# 8MIC_ximpedance_J007901D.net
KiCad netlist of a schematic drawn in EAGLE
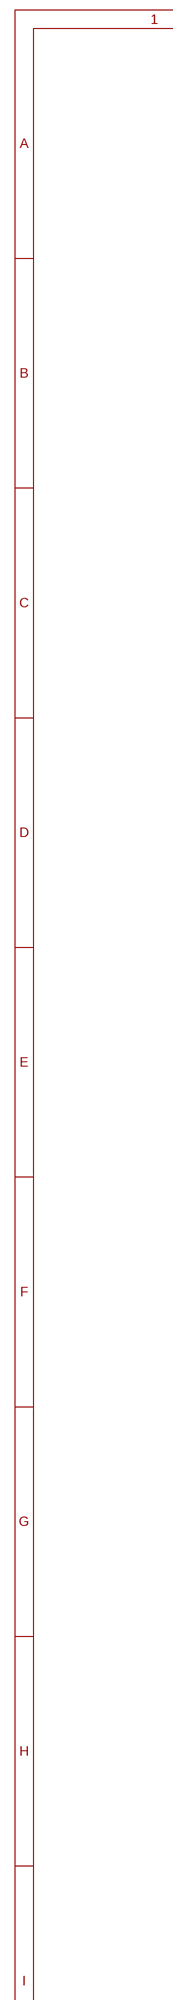
[diagram p0: schematic, sheet 1, part 1 of 2]
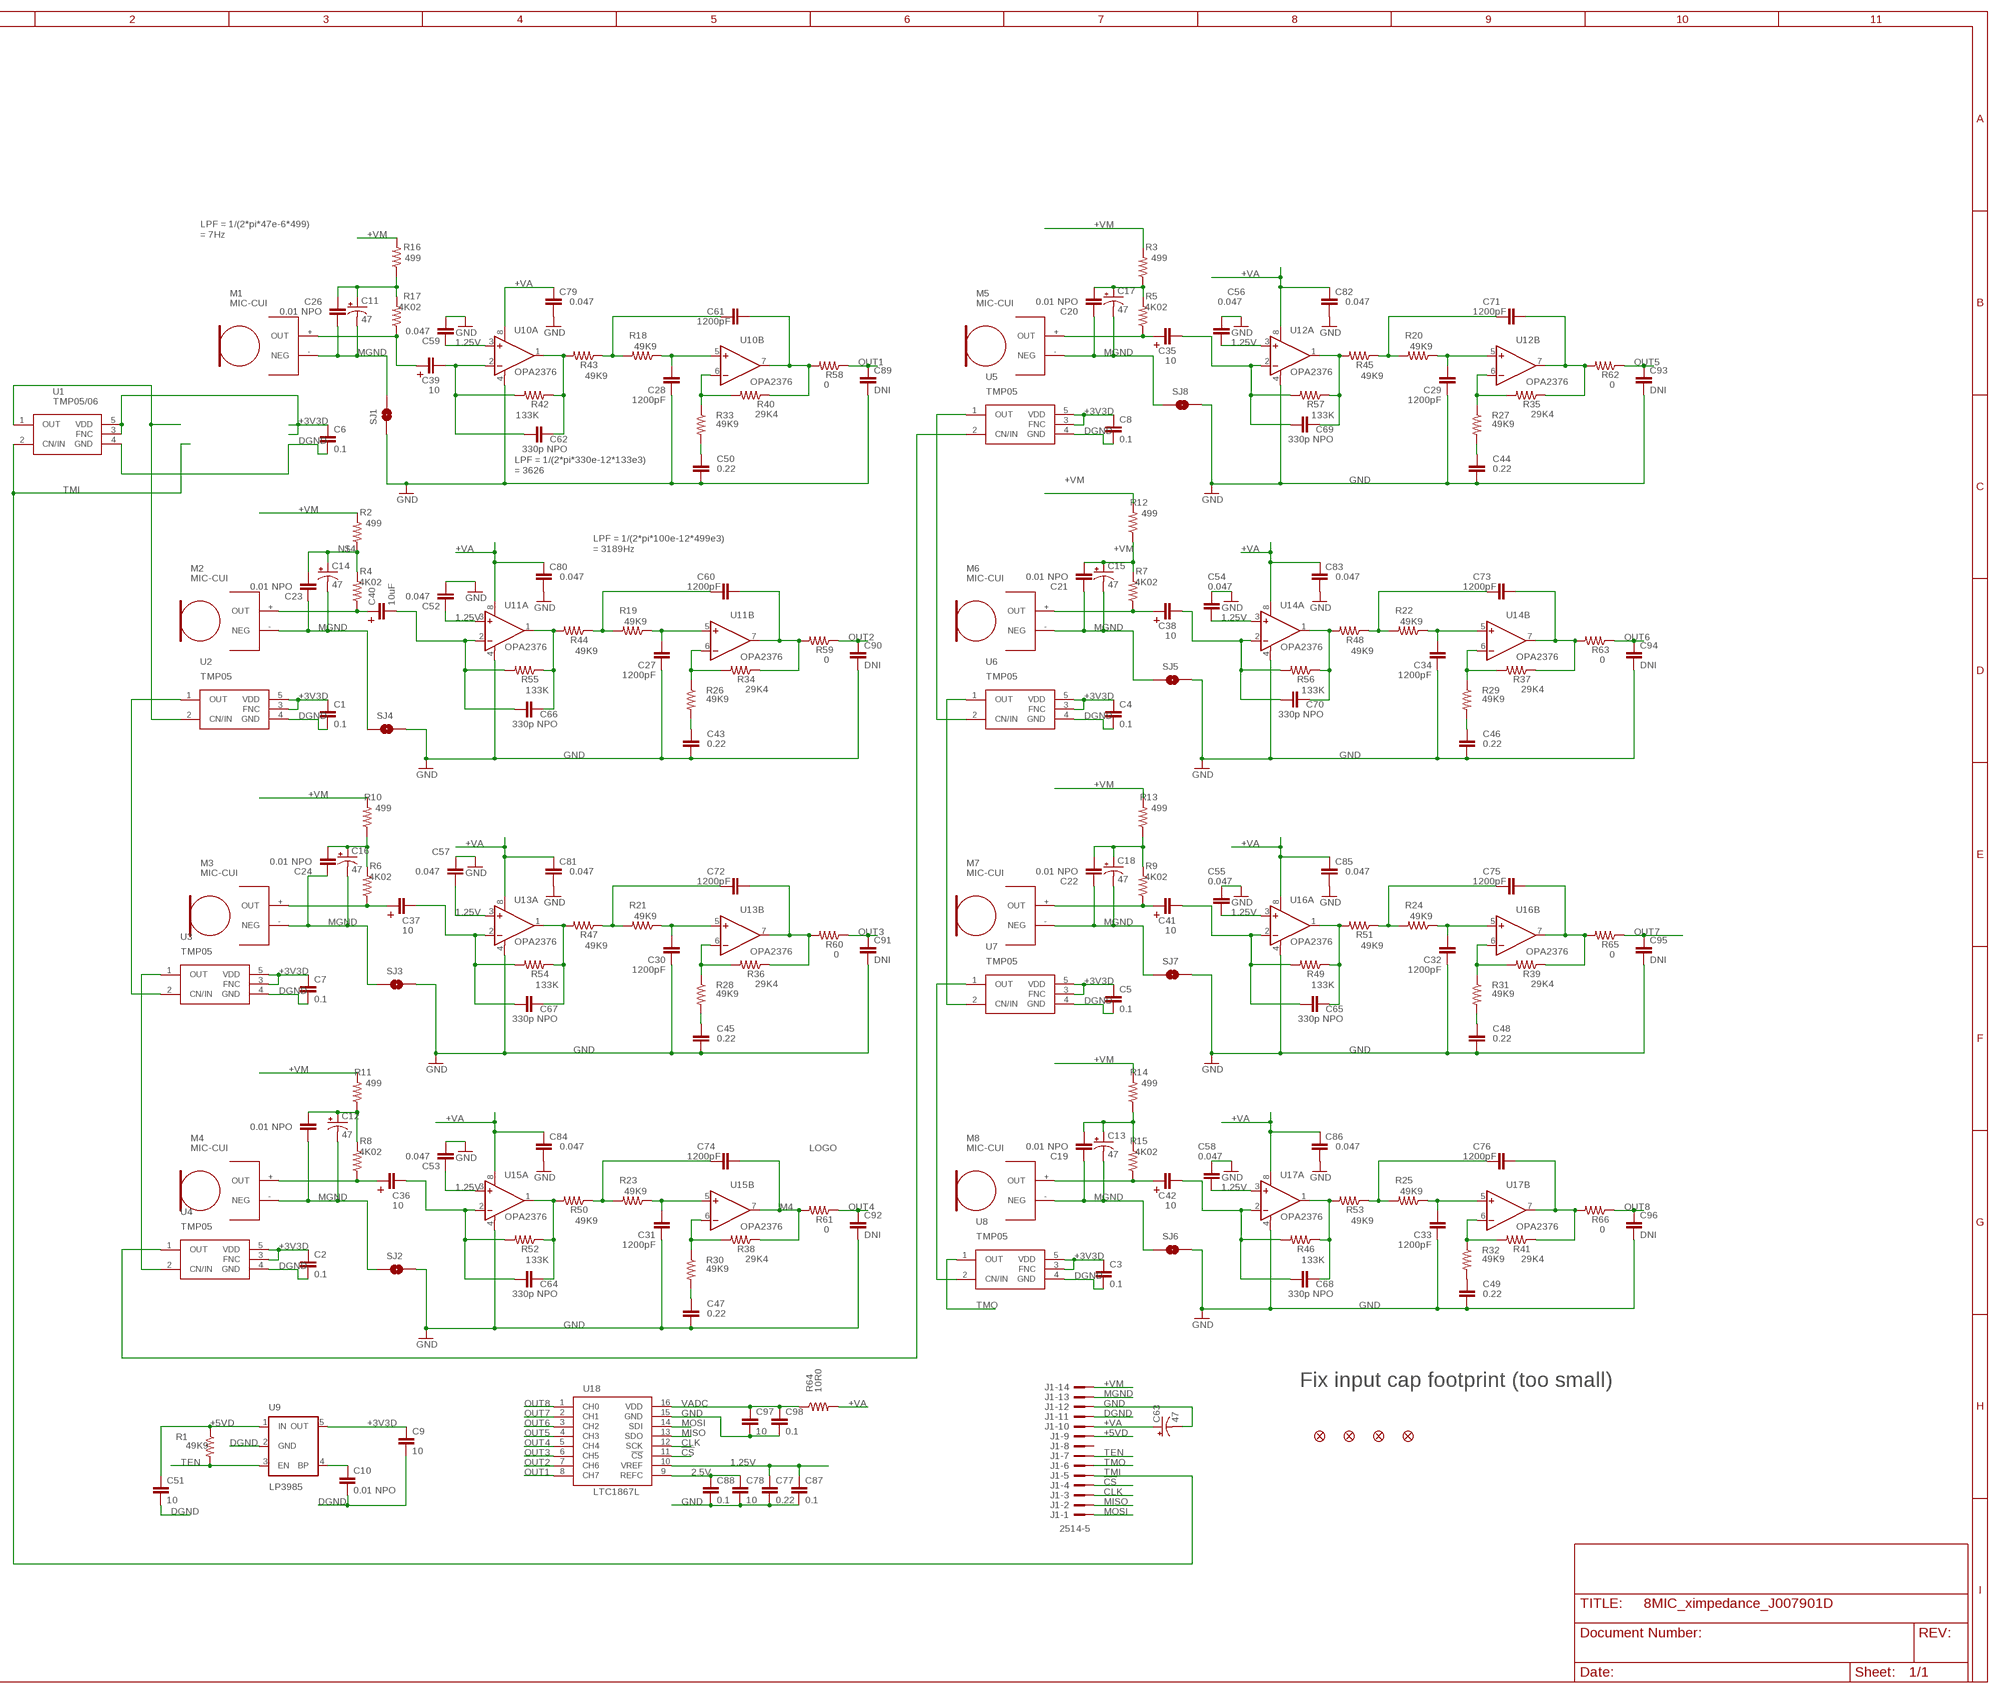
[diagram p1: schematic, sheet 1, part 2 of 2]

(export (version "E")
  (design (tool "Eeschema 10.0.6"))
  (components
    (comp (ref "C1")
      (value "0.1")
      (footprint "eagle-import:0805S")
      (libsource (lib "eagle-import") (part "CAPS0805S"))
    )
    (comp (ref "C2")
      (value "0.1")
      (footprint "eagle-import:0805S")
      (libsource (lib "eagle-import") (part "CAPS0805S"))
    )
    (comp (ref "C3")
      (value "0.1")
      (footprint "eagle-import:0805S")
      (libsource (lib "eagle-import") (part "CAPS0805S"))
    )
    (comp (ref "C4")
      (value "0.1")
      (footprint "eagle-import:0805S")
      (libsource (lib "eagle-import") (part "CAPS0805S"))
    )
    (comp (ref "C5")
      (value "0.1")
      (footprint "eagle-import:0805S")
      (libsource (lib "eagle-import") (part "CAPS0805S"))
    )
    (comp (ref "C6")
      (value "0.1")
      (footprint "eagle-import:0805S")
      (libsource (lib "eagle-import") (part "CAPS0805S"))
    )
    (comp (ref "C7")
      (value "0.1")
      (footprint "eagle-import:0805S")
      (libsource (lib "eagle-import") (part "CAPS0805S"))
    )
    (comp (ref "C8")
      (value "0.1")
      (footprint "eagle-import:0805S")
      (libsource (lib "eagle-import") (part "CAPS0805S"))
    )
    (comp (ref "C9")
      (value "10")
      (footprint "eagle-import:0805S")
      (libsource (lib "eagle-import") (part "CAPS0805S"))
    )
    (comp (ref "C10")
      (value "0.01 NPO")
      (footprint "eagle-import:0603S")
      (libsource (lib "eagle-import") (part "CAPS0603S"))
    )
    (comp (ref "C11")
      (value "47")
      (footprint "eagle-import:EIA3216")
      (libsource (lib "eagle-import") (part "CAP_POL1206"))
    )
    (comp (ref "C12")
      (value "47")
      (footprint "eagle-import:EIA3216")
      (libsource (lib "eagle-import") (part "CAP_POL1206"))
    )
    (comp (ref "C13")
      (value "47")
      (footprint "eagle-import:EIA3216")
      (libsource (lib "eagle-import") (part "CAP_POL1206"))
    )
    (comp (ref "C14")
      (value "47")
      (footprint "eagle-import:EIA3216")
      (libsource (lib "eagle-import") (part "CAP_POL1206"))
    )
    (comp (ref "C15")
      (value "47")
      (footprint "eagle-import:EIA3216")
      (libsource (lib "eagle-import") (part "CAP_POL1206"))
    )
    (comp (ref "C16")
      (value "47")
      (footprint "eagle-import:EIA3216")
      (libsource (lib "eagle-import") (part "CAP_POL1206"))
    )
    (comp (ref "C17")
      (value "47")
      (footprint "eagle-import:EIA3216")
      (libsource (lib "eagle-import") (part "CAP_POL1206"))
    )
    (comp (ref "C18")
      (value "47")
      (footprint "eagle-import:EIA3216")
      (libsource (lib "eagle-import") (part "CAP_POL1206"))
    )
    (comp (ref "C19")
      (value "0.01 NPO")
      (footprint "eagle-import:0603S")
      (libsource (lib "eagle-import") (part "CAPS0603S"))
    )
    (comp (ref "C20")
      (value "0.01 NPO")
      (footprint "eagle-import:0603S")
      (libsource (lib "eagle-import") (part "CAPS0603S"))
    )
    (comp (ref "C21")
      (value "0.01 NPO")
      (footprint "eagle-import:0603S")
      (libsource (lib "eagle-import") (part "CAPS0603S"))
    )
    (comp (ref "C22")
      (value "0.01 NPO")
      (footprint "eagle-import:0603S")
      (libsource (lib "eagle-import") (part "CAPS0603S"))
    )
    (comp (ref "C23")
      (value "0.01 NPO")
      (footprint "eagle-import:0603S")
      (libsource (lib "eagle-import") (part "CAPS0603S"))
    )
    (comp (ref "C24")
      (value "0.01 NPO")
      (footprint "eagle-import:0603S")
      (libsource (lib "eagle-import") (part "CAPS0603S"))
    )
    (comp (ref "C25")
      (value "0.01 NPO")
      (footprint "eagle-import:0603S")
      (libsource (lib "eagle-import") (part "CAPS0603S"))
    )
    (comp (ref "C26")
      (value "0.01 NPO")
      (footprint "eagle-import:0603S")
      (libsource (lib "eagle-import") (part "CAPS0603S"))
    )
    (comp (ref "C27")
      (value "1200pF")
      (footprint "eagle-import:1206S")
      (libsource (lib "eagle-import") (part "CAPS1206S"))
    )
    (comp (ref "C28")
      (value "1200pF")
      (footprint "eagle-import:1206S")
      (libsource (lib "eagle-import") (part "CAPS1206S"))
    )
    (comp (ref "C29")
      (value "1200pF")
      (footprint "eagle-import:1206S")
      (libsource (lib "eagle-import") (part "CAPS1206S"))
    )
    (comp (ref "C30")
      (value "1200pF")
      (footprint "eagle-import:1206S")
      (libsource (lib "eagle-import") (part "CAPS1206S"))
    )
    (comp (ref "C31")
      (value "1200pF")
      (footprint "eagle-import:1206S")
      (libsource (lib "eagle-import") (part "CAPS1206S"))
    )
    (comp (ref "C32")
      (value "1200pF")
      (footprint "eagle-import:1206S")
      (libsource (lib "eagle-import") (part "CAPS1206S"))
    )
    (comp (ref "C33")
      (value "1200pF")
      (footprint "eagle-import:1206S")
      (libsource (lib "eagle-import") (part "CAPS1206S"))
    )
    (comp (ref "C34")
      (value "1200pF")
      (footprint "eagle-import:1206S")
      (libsource (lib "eagle-import") (part "CAPS1206S"))
    )
    (comp (ref "C35")
      (value "10")
      (footprint "eagle-import:CAP_ELEC_A")
      (libsource (lib "eagle-import") (part "CAPS_POLCAP_E_A"))
    )
    (comp (ref "C36")
      (value "10")
      (footprint "eagle-import:CAP_ELEC_A")
      (libsource (lib "eagle-import") (part "CAPS_POLCAP_E_A"))
    )
    (comp (ref "C37")
      (value "10")
      (footprint "eagle-import:CAP_ELEC_A")
      (libsource (lib "eagle-import") (part "CAPS_POLCAP_E_A"))
    )
    (comp (ref "C38")
      (value "10")
      (footprint "eagle-import:CAP_ELEC_A")
      (libsource (lib "eagle-import") (part "CAPS_POLCAP_E_A"))
    )
    (comp (ref "C39")
      (value "10")
      (footprint "eagle-import:CAP_ELEC_A")
      (libsource (lib "eagle-import") (part "CAPS_POLCAP_E_A"))
    )
    (comp (ref "C40")
      (value "10uF")
      (footprint "eagle-import:CAP_ELEC_A")
      (libsource (lib "eagle-import") (part "CAPS_POLCAP_E_A"))
    )
    (comp (ref "C41")
      (value "10")
      (footprint "eagle-import:CAP_ELEC_A")
      (libsource (lib "eagle-import") (part "CAPS_POLCAP_E_A"))
    )
    (comp (ref "C42")
      (value "10")
      (footprint "eagle-import:CAP_ELEC_A")
      (libsource (lib "eagle-import") (part "CAPS_POLCAP_E_A"))
    )
    (comp (ref "C43")
      (value "0.22")
      (footprint "eagle-import:1206S")
      (libsource (lib "eagle-import") (part "CAPS1206S"))
    )
    (comp (ref "C44")
      (value "0.22")
      (footprint "eagle-import:1206S")
      (libsource (lib "eagle-import") (part "CAPS1206S"))
    )
    (comp (ref "C45")
      (value "0.22")
      (footprint "eagle-import:1206S")
      (libsource (lib "eagle-import") (part "CAPS1206S"))
    )
    (comp (ref "C46")
      (value "0.22")
      (footprint "eagle-import:1206S")
      (libsource (lib "eagle-import") (part "CAPS1206S"))
    )
    (comp (ref "C47")
      (value "0.22")
      (footprint "eagle-import:1206S")
      (libsource (lib "eagle-import") (part "CAPS1206S"))
    )
    (comp (ref "C48")
      (value "0.22")
      (footprint "eagle-import:1206S")
      (libsource (lib "eagle-import") (part "CAPS1206S"))
    )
    (comp (ref "C49")
      (value "0.22")
      (footprint "eagle-import:1206S")
      (libsource (lib "eagle-import") (part "CAPS1206S"))
    )
    (comp (ref "C50")
      (value "0.22")
      (footprint "eagle-import:1206S")
      (libsource (lib "eagle-import") (part "CAPS1206S"))
    )
    (comp (ref "C51")
      (value "10")
      (footprint "eagle-import:0805S")
      (libsource (lib "eagle-import") (part "CAPS0805S"))
    )
    (comp (ref "C52")
      (value "0.047")
      (footprint "eagle-import:0805S")
      (libsource (lib "eagle-import") (part "CAPS0805S"))
    )
    (comp (ref "C53")
      (value "0.047")
      (footprint "eagle-import:0805S")
      (libsource (lib "eagle-import") (part "CAPS0805S"))
    )
    (comp (ref "C54")
      (value "0.047")
      (footprint "eagle-import:0805S")
      (libsource (lib "eagle-import") (part "CAPS0805S"))
    )
    (comp (ref "C55")
      (value "0.047")
      (footprint "eagle-import:0805S")
      (libsource (lib "eagle-import") (part "CAPS0805S"))
    )
    (comp (ref "C56")
      (value "0.047")
      (footprint "eagle-import:0805S")
      (libsource (lib "eagle-import") (part "CAPS0805S"))
    )
    (comp (ref "C57")
      (value "0.047")
      (footprint "eagle-import:0805S")
      (libsource (lib "eagle-import") (part "CAPS0805S"))
    )
    (comp (ref "C58")
      (value "0.047")
      (footprint "eagle-import:0805S")
      (libsource (lib "eagle-import") (part "CAPS0805S"))
    )
    (comp (ref "C59")
      (value "0.047")
      (footprint "eagle-import:0805S")
      (libsource (lib "eagle-import") (part "CAPS0805S"))
    )
    (comp (ref "C60")
      (value "1200pF")
      (footprint "eagle-import:1206S")
      (libsource (lib "eagle-import") (part "CAPS1206S"))
    )
    (comp (ref "C61")
      (value "1200pF")
      (footprint "eagle-import:1206S")
      (libsource (lib "eagle-import") (part "CAPS1206S"))
    )
    (comp (ref "C62")
      (value "330p NPO")
      (footprint "eagle-import:0805S")
      (libsource (lib "eagle-import") (part "CAPS0805S"))
    )
    (comp (ref "C63")
      (value "47")
      (footprint "eagle-import:EIA3216")
      (libsource (lib "eagle-import") (part "CAP_POL1206"))
    )
    (comp (ref "C64")
      (value "330p NPO")
      (footprint "eagle-import:0805S")
      (libsource (lib "eagle-import") (part "CAPS0805S"))
    )
    (comp (ref "C65")
      (value "330p NPO")
      (footprint "eagle-import:0805S")
      (libsource (lib "eagle-import") (part "CAPS0805S"))
    )
    (comp (ref "C66")
      (value "330p NPO")
      (footprint "eagle-import:0805S")
      (libsource (lib "eagle-import") (part "CAPS0805S"))
    )
    (comp (ref "C67")
      (value "330p NPO")
      (footprint "eagle-import:0805S")
      (libsource (lib "eagle-import") (part "CAPS0805S"))
    )
    (comp (ref "C68")
      (value "330p NPO")
      (footprint "eagle-import:0805S")
      (libsource (lib "eagle-import") (part "CAPS0805S"))
    )
    (comp (ref "C69")
      (value "330p NPO")
      (footprint "eagle-import:0805S")
      (libsource (lib "eagle-import") (part "CAPS0805S"))
    )
    (comp (ref "C70")
      (value "330p NPO")
      (footprint "eagle-import:0805S")
      (libsource (lib "eagle-import") (part "CAPS0805S"))
    )
    (comp (ref "C71")
      (value "1200pF")
      (footprint "eagle-import:1206S")
      (libsource (lib "eagle-import") (part "CAPS1206S"))
    )
    (comp (ref "C72")
      (value "1200pF")
      (footprint "eagle-import:1206S")
      (libsource (lib "eagle-import") (part "CAPS1206S"))
    )
    (comp (ref "C73")
      (value "1200pF")
      (footprint "eagle-import:1206S")
      (libsource (lib "eagle-import") (part "CAPS1206S"))
    )
    (comp (ref "C74")
      (value "1200pF")
      (footprint "eagle-import:1206S")
      (libsource (lib "eagle-import") (part "CAPS1206S"))
    )
    (comp (ref "C75")
      (value "1200pF")
      (footprint "eagle-import:1206S")
      (libsource (lib "eagle-import") (part "CAPS1206S"))
    )
    (comp (ref "C76")
      (value "1200pF")
      (footprint "eagle-import:1206S")
      (libsource (lib "eagle-import") (part "CAPS1206S"))
    )
    (comp (ref "C77")
      (value "0.22")
      (footprint "eagle-import:C1206")
      (libsource (lib "eagle-import") (part "CC1206"))
    )
    (comp (ref "C78")
      (value "10")
      (footprint "eagle-import:0805S")
      (libsource (lib "eagle-import") (part "CAPS0805S"))
    )
    (comp (ref "C79")
      (value "0.047")
      (footprint "eagle-import:0805S")
      (libsource (lib "eagle-import") (part "CAPS0805S"))
    )
    (comp (ref "C80")
      (value "0.047")
      (footprint "eagle-import:0805S")
      (libsource (lib "eagle-import") (part "CAPS0805S"))
    )
    (comp (ref "C81")
      (value "0.047")
      (footprint "eagle-import:0805S")
      (libsource (lib "eagle-import") (part "CAPS0805S"))
    )
    (comp (ref "C82")
      (value "0.047")
      (footprint "eagle-import:0805S")
      (libsource (lib "eagle-import") (part "CAPS0805S"))
    )
    (comp (ref "C83")
      (value "0.047")
      (footprint "eagle-import:0805S")
      (libsource (lib "eagle-import") (part "CAPS0805S"))
    )
    (comp (ref "C84")
      (value "0.047")
      (footprint "eagle-import:0805S")
      (libsource (lib "eagle-import") (part "CAPS0805S"))
    )
    (comp (ref "C85")
      (value "0.047")
      (footprint "eagle-import:0805S")
      (libsource (lib "eagle-import") (part "CAPS0805S"))
    )
    (comp (ref "C86")
      (value "0.047")
      (footprint "eagle-import:0805S")
      (libsource (lib "eagle-import") (part "CAPS0805S"))
    )
    (comp (ref "C87")
      (value "0.1")
      (footprint "eagle-import:0805S")
      (libsource (lib "eagle-import") (part "CAPS0805S"))
    )
    (comp (ref "C88")
      (value "0.1")
      (footprint "eagle-import:0805S")
      (libsource (lib "eagle-import") (part "CAPS0805S"))
    )
    (comp (ref "C89")
      (value "DNI")
      (footprint "eagle-import:0603S")
      (libsource (lib "eagle-import") (part "CAPS0603S"))
    )
    (comp (ref "C90")
      (value "DNI")
      (footprint "eagle-import:0603S")
      (libsource (lib "eagle-import") (part "CAPS0603S"))
    )
    (comp (ref "C91")
      (value "DNI")
      (footprint "eagle-import:0603S")
      (libsource (lib "eagle-import") (part "CAPS0603S"))
    )
    (comp (ref "C92")
      (value "DNI")
      (footprint "eagle-import:0603S")
      (libsource (lib "eagle-import") (part "CAPS0603S"))
    )
    (comp (ref "C93")
      (value "DNI")
      (footprint "eagle-import:0603S")
      (libsource (lib "eagle-import") (part "CAPS0603S"))
    )
    (comp (ref "C94")
      (value "DNI")
      (footprint "eagle-import:0603S")
      (libsource (lib "eagle-import") (part "CAPS0603S"))
    )
    (comp (ref "C95")
      (value "DNI")
      (footprint "eagle-import:0603S")
      (libsource (lib "eagle-import") (part "CAPS0603S"))
    )
    (comp (ref "C96")
      (value "DNI")
      (footprint "eagle-import:0603S")
      (libsource (lib "eagle-import") (part "CAPS0603S"))
    )
    (comp (ref "C97")
      (value "10")
      (footprint "eagle-import:0805S")
      (libsource (lib "eagle-import") (part "CAPS0805S"))
    )
    (comp (ref "C98")
      (value "0.1")
      (footprint "eagle-import:0805S")
      (libsource (lib "eagle-import") (part "CAPS0805S"))
    )
    (comp (ref "J1")
      (value "2514-5")
      (footprint "eagle-import:PAK100_2500-5-14")
      (fields (field (name "MPN") "N2514-5002RB"))
      (libsource (lib "eagle-import") (part "2514-5"))
    )
    (comp (ref "JP1")
      (value "FIDUCIAL1.5X3")
      (footprint "eagle-import:FIDUCIAL-1.5X3")
      (libsource (lib "eagle-import") (part "FIDUCIAL1.5X3"))
    )
    (comp (ref "JP2")
      (value "FIDUCIAL1.5X3")
      (footprint "eagle-import:FIDUCIAL-1.5X3")
      (libsource (lib "eagle-import") (part "FIDUCIAL1.5X3"))
    )
    (comp (ref "JP3")
      (value "FIDUCIAL1.5X3")
      (footprint "eagle-import:FIDUCIAL-1.5X3")
      (libsource (lib "eagle-import") (part "FIDUCIAL1.5X3"))
    )
    (comp (ref "JP4")
      (value "FIDUCIAL1.5X3")
      (footprint "eagle-import:FIDUCIAL-1.5X3")
      (libsource (lib "eagle-import") (part "FIDUCIAL1.5X3"))
    )
    (comp (ref "M1")
      (value "MIC-CUI")
      (footprint "eagle-import:CUI_EDGE")
      (libsource (lib "eagle-import") (part "MIC-CUI"))
    )
    (comp (ref "M2")
      (value "MIC-CUI")
      (footprint "eagle-import:CUI_EDGE")
      (libsource (lib "eagle-import") (part "MIC-CUI"))
    )
    (comp (ref "M3")
      (value "MIC-CUI")
      (footprint "eagle-import:CUI_EDGE")
      (libsource (lib "eagle-import") (part "MIC-CUI"))
    )
    (comp (ref "M4")
      (value "MIC-CUI")
      (footprint "eagle-import:CUI_EDGE")
      (libsource (lib "eagle-import") (part "MIC-CUI"))
    )
    (comp (ref "M5")
      (value "MIC-CUI")
      (footprint "eagle-import:CUI_EDGE")
      (libsource (lib "eagle-import") (part "MIC-CUI"))
    )
    (comp (ref "M6")
      (value "MIC-CUI")
      (footprint "eagle-import:CUI_EDGE")
      (libsource (lib "eagle-import") (part "MIC-CUI"))
    )
    (comp (ref "M7")
      (value "MIC-CUI")
      (footprint "eagle-import:CUI_EDGE")
      (libsource (lib "eagle-import") (part "MIC-CUI"))
    )
    (comp (ref "M8")
      (value "MIC-CUI")
      (footprint "eagle-import:CUI_EDGE")
      (libsource (lib "eagle-import") (part "MIC-CUI"))
    )
    (comp (ref "R1")
      (value "49K9")
      (footprint "eagle-import:0603S")
      (libsource (lib "eagle-import") (part "RESISTOR_SM0603S"))
    )
    (comp (ref "R2")
      (value "499")
      (footprint "eagle-import:0603S")
      (libsource (lib "eagle-import") (part "RESISTOR_SM0603S"))
    )
    (comp (ref "R3")
      (value "499")
      (footprint "eagle-import:0603S")
      (libsource (lib "eagle-import") (part "RESISTOR_SM0603S"))
    )
    (comp (ref "R4")
      (value "4K02")
      (footprint "eagle-import:0603S")
      (libsource (lib "eagle-import") (part "RESISTOR_SM0603S"))
    )
    (comp (ref "R5")
      (value "4K02")
      (footprint "eagle-import:0603S")
      (libsource (lib "eagle-import") (part "RESISTOR_SM0603S"))
    )
    (comp (ref "R6")
      (value "4K02")
      (footprint "eagle-import:0603S")
      (libsource (lib "eagle-import") (part "RESISTOR_SM0603S"))
    )
    (comp (ref "R7")
      (value "4K02")
      (footprint "eagle-import:0603S")
      (libsource (lib "eagle-import") (part "RESISTOR_SM0603S"))
    )
    (comp (ref "R8")
      (value "4K02")
      (footprint "eagle-import:0603S")
      (libsource (lib "eagle-import") (part "RESISTOR_SM0603S"))
    )
    (comp (ref "R9")
      (value "4K02")
      (footprint "eagle-import:0603S")
      (libsource (lib "eagle-import") (part "RESISTOR_SM0603S"))
    )
    (comp (ref "R10")
      (value "499")
      (footprint "eagle-import:0603S")
      (libsource (lib "eagle-import") (part "RESISTOR_SM0603S"))
    )
    (comp (ref "R11")
      (value "499")
      (footprint "eagle-import:0603S")
      (libsource (lib "eagle-import") (part "RESISTOR_SM0603S"))
    )
    (comp (ref "R12")
      (value "499")
      (footprint "eagle-import:0603S")
      (libsource (lib "eagle-import") (part "RESISTOR_SM0603S"))
    )
    (comp (ref "R13")
      (value "499")
      (footprint "eagle-import:0603S")
      (libsource (lib "eagle-import") (part "RESISTOR_SM0603S"))
    )
    (comp (ref "R14")
      (value "499")
      (footprint "eagle-import:0603S")
      (libsource (lib "eagle-import") (part "RESISTOR_SM0603S"))
    )
    (comp (ref "R15")
      (value "4K02")
      (footprint "eagle-import:0603S")
      (libsource (lib "eagle-import") (part "RESISTOR_SM0603S"))
    )
    (comp (ref "R16")
      (value "499")
      (footprint "eagle-import:0603S")
      (libsource (lib "eagle-import") (part "RESISTOR_SM0603S"))
    )
    (comp (ref "R17")
      (value "4K02")
      (footprint "eagle-import:0603S")
      (libsource (lib "eagle-import") (part "RESISTOR_SM0603S"))
    )
    (comp (ref "R18")
      (value "49K9")
      (footprint "eagle-import:0603S")
      (libsource (lib "eagle-import") (part "RESISTOR_SM0603S"))
    )
    (comp (ref "R19")
      (value "49K9")
      (footprint "eagle-import:0603S")
      (libsource (lib "eagle-import") (part "RESISTOR_SM0603S"))
    )
    (comp (ref "R20")
      (value "49K9")
      (footprint "eagle-import:0603S")
      (libsource (lib "eagle-import") (part "RESISTOR_SM0603S"))
    )
    (comp (ref "R21")
      (value "49K9")
      (footprint "eagle-import:0603S")
      (libsource (lib "eagle-import") (part "RESISTOR_SM0603S"))
    )
    (comp (ref "R22")
      (value "49K9")
      (footprint "eagle-import:0603S")
      (libsource (lib "eagle-import") (part "RESISTOR_SM0603S"))
    )
    (comp (ref "R23")
      (value "49K9")
      (footprint "eagle-import:0603S")
      (libsource (lib "eagle-import") (part "RESISTOR_SM0603S"))
    )
    (comp (ref "R24")
      (value "49K9")
      (footprint "eagle-import:0603S")
      (libsource (lib "eagle-import") (part "RESISTOR_SM0603S"))
    )
    (comp (ref "R25")
      (value "49K9")
      (footprint "eagle-import:0603S")
      (libsource (lib "eagle-import") (part "RESISTOR_SM0603S"))
    )
    (comp (ref "R26")
      (value "49K9")
      (footprint "eagle-import:0603S")
      (libsource (lib "eagle-import") (part "RESISTOR_SM0603S"))
    )
    (comp (ref "R27")
      (value "49K9")
      (footprint "eagle-import:0603S")
      (libsource (lib "eagle-import") (part "RESISTOR_SM0603S"))
    )
    (comp (ref "R28")
      (value "49K9")
      (footprint "eagle-import:0603S")
      (libsource (lib "eagle-import") (part "RESISTOR_SM0603S"))
    )
    (comp (ref "R29")
      (value "49K9")
      (footprint "eagle-import:0603S")
      (libsource (lib "eagle-import") (part "RESISTOR_SM0603S"))
    )
    (comp (ref "R30")
      (value "49K9")
      (footprint "eagle-import:0603S")
      (libsource (lib "eagle-import") (part "RESISTOR_SM0603S"))
    )
    (comp (ref "R31")
      (value "49K9")
      (footprint "eagle-import:0603S")
      (libsource (lib "eagle-import") (part "RESISTOR_SM0603S"))
    )
    (comp (ref "R32")
      (value "49K9")
      (footprint "eagle-import:0603S")
      (libsource (lib "eagle-import") (part "RESISTOR_SM0603S"))
    )
    (comp (ref "R33")
      (value "49K9")
      (footprint "eagle-import:0603S")
      (libsource (lib "eagle-import") (part "RESISTOR_SM0603S"))
    )
    (comp (ref "R34")
      (value "29K4")
      (footprint "eagle-import:0603S")
      (libsource (lib "eagle-import") (part "RESISTOR_SM0603S"))
    )
    (comp (ref "R35")
      (value "29K4")
      (footprint "eagle-import:0603S")
      (libsource (lib "eagle-import") (part "RESISTOR_SM0603S"))
    )
    (comp (ref "R36")
      (value "29K4")
      (footprint "eagle-import:0603S")
      (libsource (lib "eagle-import") (part "RESISTOR_SM0603S"))
    )
    (comp (ref "R37")
      (value "29K4")
      (footprint "eagle-import:0603S")
      (libsource (lib "eagle-import") (part "RESISTOR_SM0603S"))
    )
    (comp (ref "R38")
      (value "29K4")
      (footprint "eagle-import:0603S")
      (libsource (lib "eagle-import") (part "RESISTOR_SM0603S"))
    )
    (comp (ref "R39")
      (value "29K4")
      (footprint "eagle-import:0603S")
      (libsource (lib "eagle-import") (part "RESISTOR_SM0603S"))
    )
    (comp (ref "R40")
      (value "29K4")
      (footprint "eagle-import:0603S")
      (libsource (lib "eagle-import") (part "RESISTOR_SM0603S"))
    )
    (comp (ref "R41")
      (value "29K4")
      (footprint "eagle-import:0603S")
      (libsource (lib "eagle-import") (part "RESISTOR_SM0603S"))
    )
    (comp (ref "R42")
      (value "133K")
      (footprint "eagle-import:0603S")
      (libsource (lib "eagle-import") (part "RESISTOR_SM0603S"))
    )
    (comp (ref "R43")
      (value "49K9")
      (footprint "eagle-import:0603S")
      (libsource (lib "eagle-import") (part "RESISTOR_SM0603S"))
    )
    (comp (ref "R44")
      (value "49K9")
      (footprint "eagle-import:0603S")
      (libsource (lib "eagle-import") (part "RESISTOR_SM0603S"))
    )
    (comp (ref "R45")
      (value "49K9")
      (footprint "eagle-import:0603S")
      (libsource (lib "eagle-import") (part "RESISTOR_SM0603S"))
    )
    (comp (ref "R46")
      (value "133K")
      (footprint "eagle-import:0603S")
      (libsource (lib "eagle-import") (part "RESISTOR_SM0603S"))
    )
    (comp (ref "R47")
      (value "49K9")
      (footprint "eagle-import:0603S")
      (libsource (lib "eagle-import") (part "RESISTOR_SM0603S"))
    )
    (comp (ref "R48")
      (value "49K9")
      (footprint "eagle-import:0603S")
      (libsource (lib "eagle-import") (part "RESISTOR_SM0603S"))
    )
    (comp (ref "R49")
      (value "133K")
      (footprint "eagle-import:0603S")
      (libsource (lib "eagle-import") (part "RESISTOR_SM0603S"))
    )
    (comp (ref "R50")
      (value "49K9")
      (footprint "eagle-import:0603S")
      (libsource (lib "eagle-import") (part "RESISTOR_SM0603S"))
    )
    (comp (ref "R51")
      (value "49K9")
      (footprint "eagle-import:0603S")
      (libsource (lib "eagle-import") (part "RESISTOR_SM0603S"))
    )
    (comp (ref "R52")
      (value "133K")
      (footprint "eagle-import:0603S")
      (libsource (lib "eagle-import") (part "RESISTOR_SM0603S"))
    )
    (comp (ref "R53")
      (value "49K9")
      (footprint "eagle-import:0603S")
      (libsource (lib "eagle-import") (part "RESISTOR_SM0603S"))
    )
    (comp (ref "R54")
      (value "133K")
      (footprint "eagle-import:0603S")
      (libsource (lib "eagle-import") (part "RESISTOR_SM0603S"))
    )
    (comp (ref "R55")
      (value "133K")
      (footprint "eagle-import:0603S")
      (libsource (lib "eagle-import") (part "RESISTOR_SM0603S"))
    )
    (comp (ref "R56")
      (value "133K")
      (footprint "eagle-import:0603S")
      (libsource (lib "eagle-import") (part "RESISTOR_SM0603S"))
    )
    (comp (ref "R57")
      (value "133K")
      (footprint "eagle-import:0603S")
      (libsource (lib "eagle-import") (part "RESISTOR_SM0603S"))
    )
    (comp (ref "R58")
      (value "0")
      (footprint "eagle-import:0603S")
      (libsource (lib "eagle-import") (part "RESISTOR_SM0603S"))
    )
    (comp (ref "R59")
      (value "0")
      (footprint "eagle-import:0603S")
      (libsource (lib "eagle-import") (part "RESISTOR_SM0603S"))
    )
    (comp (ref "R60")
      (value "0")
      (footprint "eagle-import:0603S")
      (libsource (lib "eagle-import") (part "RESISTOR_SM0603S"))
    )
    (comp (ref "R61")
      (value "0")
      (footprint "eagle-import:0603S")
      (libsource (lib "eagle-import") (part "RESISTOR_SM0603S"))
    )
    (comp (ref "R62")
      (value "0")
      (footprint "eagle-import:0603S")
      (libsource (lib "eagle-import") (part "RESISTOR_SM0603S"))
    )
    (comp (ref "R63")
      (value "0")
      (footprint "eagle-import:0603S")
      (libsource (lib "eagle-import") (part "RESISTOR_SM0603S"))
    )
    (comp (ref "R64")
      (value "10R0")
      (footprint "eagle-import:0603S")
      (libsource (lib "eagle-import") (part "RESISTOR_SM0603S"))
    )
    (comp (ref "R65")
      (value "0")
      (footprint "eagle-import:0603S")
      (libsource (lib "eagle-import") (part "RESISTOR_SM0603S"))
    )
    (comp (ref "R66")
      (value "0")
      (footprint "eagle-import:0603S")
      (libsource (lib "eagle-import") (part "RESISTOR_SM0603S"))
    )
    (comp (ref "SJ1")
      (value "SOLDERJUMPERTRACE")
      (footprint "eagle-import:SJ_2S-TRACE")
      (libsource (lib "eagle-import") (part "SOLDERJUMPERTRACE"))
    )
    (comp (ref "SJ2")
      (value "SOLDERJUMPERTRACE")
      (footprint "eagle-import:SJ_2S-TRACE")
      (libsource (lib "eagle-import") (part "SOLDERJUMPERTRACE"))
    )
    (comp (ref "SJ3")
      (value "SOLDERJUMPERTRACE")
      (footprint "eagle-import:SJ_2S-TRACE")
      (libsource (lib "eagle-import") (part "SOLDERJUMPERTRACE"))
    )
    (comp (ref "SJ4")
      (value "SOLDERJUMPERTRACE")
      (footprint "eagle-import:SJ_2S-TRACE")
      (libsource (lib "eagle-import") (part "SOLDERJUMPERTRACE"))
    )
    (comp (ref "SJ5")
      (value "SOLDERJUMPERTRACE")
      (footprint "eagle-import:SJ_2S-TRACE")
      (libsource (lib "eagle-import") (part "SOLDERJUMPERTRACE"))
    )
    (comp (ref "SJ6")
      (value "SOLDERJUMPERTRACE")
      (footprint "eagle-import:SJ_2S-TRACE")
      (libsource (lib "eagle-import") (part "SOLDERJUMPERTRACE"))
    )
    (comp (ref "SJ7")
      (value "SOLDERJUMPERTRACE")
      (footprint "eagle-import:SJ_2S-TRACE")
      (libsource (lib "eagle-import") (part "SOLDERJUMPERTRACE"))
    )
    (comp (ref "SJ8")
      (value "SOLDERJUMPERTRACE")
      (footprint "eagle-import:SJ_2S-TRACE")
      (libsource (lib "eagle-import") (part "SOLDERJUMPERTRACE"))
    )
    (comp (ref "U$1")
      (value "JFRC-LOGOLOGO_OP")
      (footprint "eagle-import:LOGO_BMP_OP")
      (libsource (lib "eagle-import") (part "JFRC-LOGOLOGO_OP"))
    )
    (comp (ref "U1")
      (value "TMP05/06")
      (footprint "eagle-import:SOT-SC-5")
      (libsource (lib "eagle-import") (part "TMP05/06"))
    )
    (comp (ref "U2")
      (value "TMP05")
      (footprint "eagle-import:SOT23-5")
      (libsource (lib "eagle-import") (part "analog-devices_sws_TMP05/06"))
    )
    (comp (ref "U3")
      (value "TMP05")
      (footprint "eagle-import:SOT23-5")
      (libsource (lib "eagle-import") (part "analog-devices_sws_TMP05/06"))
    )
    (comp (ref "U4")
      (value "TMP05")
      (footprint "eagle-import:SOT23-5")
      (libsource (lib "eagle-import") (part "analog-devices_sws_TMP05/06"))
    )
    (comp (ref "U5")
      (value "TMP05")
      (footprint "eagle-import:SOT23-5")
      (libsource (lib "eagle-import") (part "analog-devices_sws_TMP05/06"))
    )
    (comp (ref "U6")
      (value "TMP05")
      (footprint "eagle-import:SOT23-5")
      (libsource (lib "eagle-import") (part "analog-devices_sws_TMP05/06"))
    )
    (comp (ref "U7")
      (value "TMP05")
      (footprint "eagle-import:SOT23-5")
      (libsource (lib "eagle-import") (part "analog-devices_sws_TMP05/06"))
    )
    (comp (ref "U8")
      (value "TMP05")
      (footprint "eagle-import:SOT23-5")
      (libsource (lib "eagle-import") (part "analog-devices_sws_TMP05/06"))
    )
    (comp (ref "U9")
      (value "LP3985")
      (footprint "eagle-import:SOT23-5")
      (libsource (lib "eagle-import") (part "MIC5203SMD"))
    )
    (comp (ref "U10")
      (value "OPA2376")
      (footprint "eagle-import:MSOP08")
      (fields (field (name "MF") "TEXAS INSTRUMENTS") (field (name "MPN") "OPA2237EA/250"))
      (libsource (lib "eagle-import") (part "OPA2237E"))
    )
    (comp (ref "U11")
      (value "OPA2376")
      (footprint "eagle-import:MSOP08")
      (fields (field (name "MF") "TEXAS INSTRUMENTS") (field (name "MPN") "OPA2237EA/250"))
      (libsource (lib "eagle-import") (part "OPA2237E"))
    )
    (comp (ref "U12")
      (value "OPA2376")
      (footprint "eagle-import:MSOP08")
      (fields (field (name "MF") "TEXAS INSTRUMENTS") (field (name "MPN") "OPA2237EA/250"))
      (libsource (lib "eagle-import") (part "OPA2237E"))
    )
    (comp (ref "U13")
      (value "OPA2376")
      (footprint "eagle-import:MSOP08")
      (fields (field (name "MF") "TEXAS INSTRUMENTS") (field (name "MPN") "OPA2237EA/250"))
      (libsource (lib "eagle-import") (part "OPA2237E"))
    )
    (comp (ref "U14")
      (value "OPA2376")
      (footprint "eagle-import:MSOP08")
      (fields (field (name "MF") "TEXAS INSTRUMENTS") (field (name "MPN") "OPA2237EA/250"))
      (libsource (lib "eagle-import") (part "OPA2237E"))
    )
    (comp (ref "U15")
      (value "OPA2376")
      (footprint "eagle-import:MSOP08")
      (fields (field (name "MF") "TEXAS INSTRUMENTS") (field (name "MPN") "OPA2237EA/250"))
      (libsource (lib "eagle-import") (part "OPA2237E"))
    )
    (comp (ref "U16")
      (value "OPA2376")
      (footprint "eagle-import:MSOP08")
      (fields (field (name "MF") "TEXAS INSTRUMENTS") (field (name "MPN") "OPA2237EA/250"))
      (libsource (lib "eagle-import") (part "OPA2237E"))
    )
    (comp (ref "U17")
      (value "OPA2376")
      (footprint "eagle-import:MSOP08")
      (fields (field (name "MF") "TEXAS INSTRUMENTS") (field (name "MPN") "OPA2237EA/250"))
      (libsource (lib "eagle-import") (part "OPA2237E"))
    )
    (comp (ref "U18")
      (value "LTC1867L")
      (footprint "eagle-import:SSOP16")
      (libsource (lib "eagle-import") (part "LTC1867"))
    )
  )
  (nets
    (net (code "1") (name "/+3V3D") (class "Default")
      (node (ref "C1") (pin "1") (pinfunction "1_1") (pintype "passive"))
      (node (ref "C2") (pin "1") (pinfunction "1_1") (pintype "passive"))
      (node (ref "C3") (pin "1") (pinfunction "1_1") (pintype "passive"))
      (node (ref "C4") (pin "1") (pinfunction "1_1") (pintype "passive"))
      (node (ref "C5") (pin "1") (pinfunction "1_1") (pintype "passive"))
      (node (ref "C6") (pin "1") (pinfunction "1_1") (pintype "passive"))
      (node (ref "C7") (pin "1") (pinfunction "1_1") (pintype "passive"))
      (node (ref "C8") (pin "1") (pinfunction "1_1") (pintype "passive"))
      (node (ref "C9") (pin "1") (pinfunction "1_1") (pintype "passive"))
      (node (ref "U1") (pin "3") (pinfunction "FNC_3") (pintype "bidirectional"))
      (node (ref "U1") (pin "5") (pinfunction "VDD_5") (pintype "bidirectional"))
      (node (ref "U2") (pin "3") (pinfunction "FNC_3") (pintype "bidirectional"))
      (node (ref "U2") (pin "5") (pinfunction "VDD_5") (pintype "bidirectional"))
      (node (ref "U3") (pin "3") (pinfunction "FNC_3") (pintype "bidirectional"))
      (node (ref "U3") (pin "5") (pinfunction "VDD_5") (pintype "bidirectional"))
      (node (ref "U4") (pin "3") (pinfunction "FNC_3") (pintype "bidirectional"))
      (node (ref "U4") (pin "5") (pinfunction "VDD_5") (pintype "bidirectional"))
      (node (ref "U5") (pin "3") (pinfunction "FNC_3") (pintype "bidirectional"))
      (node (ref "U5") (pin "5") (pinfunction "VDD_5") (pintype "bidirectional"))
      (node (ref "U6") (pin "3") (pinfunction "FNC_3") (pintype "bidirectional"))
      (node (ref "U6") (pin "5") (pinfunction "VDD_5") (pintype "bidirectional"))
      (node (ref "U7") (pin "3") (pinfunction "FNC_3") (pintype "bidirectional"))
      (node (ref "U7") (pin "5") (pinfunction "VDD_5") (pintype "bidirectional"))
      (node (ref "U8") (pin "3") (pinfunction "FNC_3") (pintype "bidirectional"))
      (node (ref "U8") (pin "5") (pinfunction "VDD_5") (pintype "bidirectional"))
      (node (ref "U9") (pin "5") (pinfunction "OUT_5") (pintype "passive"))
    )
    (net (code "2") (name "/+5VD") (class "Default")
      (node (ref "C51") (pin "1") (pinfunction "1_1") (pintype "passive"))
      (node (ref "J1") (pin "9") (pinfunction "KL_9") (pintype "passive"))
      (node (ref "R1") (pin "1") (pinfunction "1_1") (pintype "passive"))
      (node (ref "U9") (pin "1") (pinfunction "IN_1") (pintype "input"))
    )
    (net (code "3") (name "/+VA") (class "Default")
      (node (ref "C63") (pin "A") (pinfunction "+_A") (pintype "passive"))
      (node (ref "C79") (pin "2") (pinfunction "2_2") (pintype "passive"))
      (node (ref "C80") (pin "2") (pinfunction "2_2") (pintype "passive"))
      (node (ref "C81") (pin "2") (pinfunction "2_2") (pintype "passive"))
      (node (ref "C82") (pin "2") (pinfunction "2_2") (pintype "passive"))
      (node (ref "C83") (pin "2") (pinfunction "2_2") (pintype "passive"))
      (node (ref "C84") (pin "2") (pinfunction "2_2") (pintype "passive"))
      (node (ref "C85") (pin "2") (pinfunction "2_2") (pintype "passive"))
      (node (ref "C86") (pin "2") (pinfunction "2_2") (pintype "passive"))
      (node (ref "J1") (pin "10") (pinfunction "KL_10") (pintype "passive"))
      (node (ref "R64") (pin "2") (pinfunction "2_2") (pintype "passive"))
      (node (ref "U10") (pin "8") (pinfunction "V+_8") (pintype "power_in"))
      (node (ref "U11") (pin "8") (pinfunction "V+_8") (pintype "power_in"))
      (node (ref "U12") (pin "8") (pinfunction "V+_8") (pintype "power_in"))
      (node (ref "U13") (pin "8") (pinfunction "V+_8") (pintype "power_in"))
      (node (ref "U14") (pin "8") (pinfunction "V+_8") (pintype "power_in"))
      (node (ref "U15") (pin "8") (pinfunction "V+_8") (pintype "power_in"))
      (node (ref "U16") (pin "8") (pinfunction "V+_8") (pintype "power_in"))
      (node (ref "U17") (pin "8") (pinfunction "V+_8") (pintype "power_in"))
    )
    (net (code "4") (name "/+VM") (class "Default")
      (node (ref "J1") (pin "14") (pinfunction "KL_14") (pintype "passive"))
      (node (ref "R10") (pin "2") (pinfunction "2_2") (pintype "passive"))
      (node (ref "R11") (pin "2") (pinfunction "2_2") (pintype "passive"))
      (node (ref "R12") (pin "2") (pinfunction "2_2") (pintype "passive"))
      (node (ref "R13") (pin "2") (pinfunction "2_2") (pintype "passive"))
      (node (ref "R14") (pin "2") (pinfunction "2_2") (pintype "passive"))
      (node (ref "R16") (pin "2") (pinfunction "2_2") (pintype "passive"))
      (node (ref "R2") (pin "2") (pinfunction "2_2") (pintype "passive"))
      (node (ref "R3") (pin "2") (pinfunction "2_2") (pintype "passive"))
    )
    (net (code "5") (name "/1.25V") (class "Default")
      (node (ref "C52") (pin "2") (pinfunction "2_2") (pintype "passive"))
      (node (ref "C53") (pin "2") (pinfunction "2_2") (pintype "passive"))
      (node (ref "C54") (pin "2") (pinfunction "2_2") (pintype "passive"))
      (node (ref "C55") (pin "2") (pinfunction "2_2") (pintype "passive"))
      (node (ref "C56") (pin "2") (pinfunction "2_2") (pintype "passive"))
      (node (ref "C57") (pin "2") (pinfunction "2_2") (pintype "passive"))
      (node (ref "C58") (pin "2") (pinfunction "2_2") (pintype "passive"))
      (node (ref "C59") (pin "2") (pinfunction "2_2") (pintype "passive"))
      (node (ref "C77") (pin "1") (pinfunction "1_1") (pintype "passive"))
      (node (ref "C87") (pin "1") (pinfunction "1_1") (pintype "passive"))
      (node (ref "U10") (pin "3") (pinfunction "+IN_3") (pintype "input"))
      (node (ref "U11") (pin "3") (pinfunction "+IN_3") (pintype "input"))
      (node (ref "U12") (pin "3") (pinfunction "+IN_3") (pintype "input"))
      (node (ref "U13") (pin "3") (pinfunction "+IN_3") (pintype "input"))
      (node (ref "U14") (pin "3") (pinfunction "+IN_3") (pintype "input"))
      (node (ref "U15") (pin "3") (pinfunction "+IN_3") (pintype "input"))
      (node (ref "U16") (pin "3") (pinfunction "+IN_3") (pintype "input"))
      (node (ref "U17") (pin "3") (pinfunction "+IN_3") (pintype "input"))
      (node (ref "U18") (pin "10") (pinfunction "VREF_10") (pintype "bidirectional"))
    )
    (net (code "6") (name "/2.5V") (class "Default")
      (node (ref "C78") (pin "1") (pinfunction "1_1") (pintype "passive"))
      (node (ref "C88") (pin "1") (pinfunction "1_1") (pintype "passive"))
      (node (ref "U18") (pin "9") (pinfunction "REFC_9") (pintype "bidirectional"))
    )
    (net (code "7") (name "/CLK") (class "Default")
      (node (ref "J1") (pin "3") (pinfunction "KL_3") (pintype "passive"))
      (node (ref "U18") (pin "12") (pinfunction "SCK_12") (pintype "bidirectional"))
    )
    (net (code "8") (name "/DGND") (class "Default")
      (node (ref "C1") (pin "2") (pinfunction "2_2") (pintype "passive"))
      (node (ref "C10") (pin "2") (pinfunction "2_2") (pintype "passive"))
      (node (ref "C2") (pin "2") (pinfunction "2_2") (pintype "passive"))
      (node (ref "C3") (pin "2") (pinfunction "2_2") (pintype "passive"))
      (node (ref "C4") (pin "2") (pinfunction "2_2") (pintype "passive"))
      (node (ref "C5") (pin "2") (pinfunction "2_2") (pintype "passive"))
      (node (ref "C51") (pin "2") (pinfunction "2_2") (pintype "passive"))
      (node (ref "C6") (pin "2") (pinfunction "2_2") (pintype "passive"))
      (node (ref "C7") (pin "2") (pinfunction "2_2") (pintype "passive"))
      (node (ref "C8") (pin "2") (pinfunction "2_2") (pintype "passive"))
      (node (ref "C9") (pin "2") (pinfunction "2_2") (pintype "passive"))
      (node (ref "J1") (pin "11") (pinfunction "KL_11") (pintype "passive"))
      (node (ref "U1") (pin "4") (pinfunction "GND_4") (pintype "bidirectional"))
      (node (ref "U2") (pin "4") (pinfunction "GND_4") (pintype "bidirectional"))
      (node (ref "U3") (pin "4") (pinfunction "GND_4") (pintype "bidirectional"))
      (node (ref "U4") (pin "4") (pinfunction "GND_4") (pintype "bidirectional"))
      (node (ref "U5") (pin "4") (pinfunction "GND_4") (pintype "bidirectional"))
      (node (ref "U6") (pin "4") (pinfunction "GND_4") (pintype "bidirectional"))
      (node (ref "U7") (pin "4") (pinfunction "GND_4") (pintype "bidirectional"))
      (node (ref "U8") (pin "4") (pinfunction "GND_4") (pintype "bidirectional"))
      (node (ref "U9") (pin "2") (pinfunction "GND_2") (pintype "input"))
    )
    (net (code "9") (name "/M4") (class "Default")
      (node (ref "C74") (pin "1") (pinfunction "1_1") (pintype "passive"))
      (node (ref "R38") (pin "1") (pinfunction "1_1") (pintype "passive"))
      (node (ref "R61") (pin "2") (pinfunction "2_2") (pintype "passive"))
      (node (ref "U15") (pin "7") (pinfunction "OUT_7") (pintype "output"))
    )
    (net (code "10") (name "/MGND") (class "Default")
      (node (ref "C11") (pin "C") (pinfunction "-_C") (pintype "passive"))
      (node (ref "C12") (pin "C") (pinfunction "-_C") (pintype "passive"))
      (node (ref "C13") (pin "C") (pinfunction "-_C") (pintype "passive"))
      (node (ref "C14") (pin "C") (pinfunction "-_C") (pintype "passive"))
      (node (ref "C15") (pin "C") (pinfunction "-_C") (pintype "passive"))
      (node (ref "C16") (pin "C") (pinfunction "-_C") (pintype "passive"))
      (node (ref "C17") (pin "C") (pinfunction "-_C") (pintype "passive"))
      (node (ref "C18") (pin "C") (pinfunction "-_C") (pintype "passive"))
      (node (ref "C19") (pin "2") (pinfunction "2_2") (pintype "passive"))
      (node (ref "C20") (pin "2") (pinfunction "2_2") (pintype "passive"))
      (node (ref "C21") (pin "2") (pinfunction "2_2") (pintype "passive"))
      (node (ref "C22") (pin "2") (pinfunction "2_2") (pintype "passive"))
      (node (ref "C23") (pin "2") (pinfunction "2_2") (pintype "passive"))
      (node (ref "C24") (pin "2") (pinfunction "2_2") (pintype "passive"))
      (node (ref "C25") (pin "2") (pinfunction "2_2") (pintype "passive"))
      (node (ref "C26") (pin "2") (pinfunction "2_2") (pintype "passive"))
      (node (ref "J1") (pin "13") (pinfunction "KL_13") (pintype "passive"))
      (node (ref "M1") (pin "-") (pinfunction "NEG_-") (pintype "bidirectional"))
      (node (ref "M2") (pin "-") (pinfunction "NEG_-") (pintype "bidirectional"))
      (node (ref "M3") (pin "-") (pinfunction "NEG_-") (pintype "bidirectional"))
      (node (ref "M4") (pin "-") (pinfunction "NEG_-") (pintype "bidirectional"))
      (node (ref "M5") (pin "-") (pinfunction "NEG_-") (pintype "bidirectional"))
      (node (ref "M6") (pin "-") (pinfunction "NEG_-") (pintype "bidirectional"))
      (node (ref "M7") (pin "-") (pinfunction "NEG_-") (pintype "bidirectional"))
      (node (ref "M8") (pin "-") (pinfunction "NEG_-") (pintype "bidirectional"))
      (node (ref "SJ1") (pin "2") (pinfunction "2_2") (pintype "passive"))
      (node (ref "SJ2") (pin "1") (pinfunction "1_1") (pintype "passive"))
      (node (ref "SJ3") (pin "1") (pinfunction "1_1") (pintype "passive"))
      (node (ref "SJ4") (pin "1") (pinfunction "1_1") (pintype "passive"))
      (node (ref "SJ5") (pin "1") (pinfunction "1_1") (pintype "passive"))
      (node (ref "SJ6") (pin "1") (pinfunction "1_1") (pintype "passive"))
      (node (ref "SJ7") (pin "1") (pinfunction "1_1") (pintype "passive"))
      (node (ref "SJ8") (pin "1") (pinfunction "1_1") (pintype "passive"))
    )
    (net (code "11") (name "/MISO") (class "Default")
      (node (ref "J1") (pin "2") (pinfunction "KL_2") (pintype "passive"))
      (node (ref "U18") (pin "13") (pinfunction "SDO_13") (pintype "bidirectional"))
    )
    (net (code "12") (name "/MOSI") (class "Default")
      (node (ref "J1") (pin "1") (pinfunction "KL_1") (pintype "passive"))
      (node (ref "U18") (pin "14") (pinfunction "SDI_14") (pintype "bidirectional"))
    )
    (net (code "13") (name "/N$4") (class "Default")
      (node (ref "C14") (pin "A") (pinfunction "+_A") (pintype "passive"))
      (node (ref "C23") (pin "1") (pinfunction "1_1") (pintype "passive"))
      (node (ref "R2") (pin "1") (pinfunction "1_1") (pintype "passive"))
      (node (ref "R4") (pin "2") (pinfunction "2_2") (pintype "passive"))
    )
    (net (code "14") (name "/OUT1") (class "Default")
      (node (ref "C89") (pin "1") (pinfunction "1_1") (pintype "passive"))
      (node (ref "R58") (pin "1") (pinfunction "1_1") (pintype "passive"))
      (node (ref "U18") (pin "8") (pinfunction "CH7_8") (pintype "bidirectional"))
    )
    (net (code "15") (name "/OUT2") (class "Default")
      (node (ref "C90") (pin "1") (pinfunction "1_1") (pintype "passive"))
      (node (ref "R59") (pin "1") (pinfunction "1_1") (pintype "passive"))
      (node (ref "U18") (pin "7") (pinfunction "CH6_7") (pintype "bidirectional"))
    )
    (net (code "16") (name "/OUT3") (class "Default")
      (node (ref "C91") (pin "1") (pinfunction "1_1") (pintype "passive"))
      (node (ref "R60") (pin "1") (pinfunction "1_1") (pintype "passive"))
      (node (ref "U18") (pin "6") (pinfunction "CH5_6") (pintype "bidirectional"))
    )
    (net (code "17") (name "/OUT4") (class "Default")
      (node (ref "C92") (pin "1") (pinfunction "1_1") (pintype "passive"))
      (node (ref "R61") (pin "1") (pinfunction "1_1") (pintype "passive"))
      (node (ref "U18") (pin "5") (pinfunction "CH4_5") (pintype "bidirectional"))
    )
    (net (code "18") (name "/OUT5") (class "Default")
      (node (ref "C93") (pin "1") (pinfunction "1_1") (pintype "passive"))
      (node (ref "R62") (pin "1") (pinfunction "1_1") (pintype "passive"))
      (node (ref "U18") (pin "4") (pinfunction "CH3_4") (pintype "bidirectional"))
    )
    (net (code "19") (name "/OUT6") (class "Default")
      (node (ref "C94") (pin "1") (pinfunction "1_1") (pintype "passive"))
      (node (ref "R63") (pin "1") (pinfunction "1_1") (pintype "passive"))
      (node (ref "U18") (pin "3") (pinfunction "CH2_3") (pintype "bidirectional"))
    )
    (net (code "20") (name "/OUT7") (class "Default")
      (node (ref "C95") (pin "1") (pinfunction "1_1") (pintype "passive"))
      (node (ref "R65") (pin "1") (pinfunction "1_1") (pintype "passive"))
      (node (ref "U18") (pin "2") (pinfunction "CH1_2") (pintype "bidirectional"))
    )
    (net (code "21") (name "/OUT8") (class "Default")
      (node (ref "C96") (pin "1") (pinfunction "1_1") (pintype "passive"))
      (node (ref "R66") (pin "1") (pinfunction "1_1") (pintype "passive"))
      (node (ref "U18") (pin "1") (pinfunction "CH0_1") (pintype "bidirectional"))
    )
    (net (code "22") (name "/TEN") (class "Default")
      (node (ref "J1") (pin "7") (pinfunction "KL_7") (pintype "passive"))
      (node (ref "R1") (pin "2") (pinfunction "2_2") (pintype "passive"))
      (node (ref "U9") (pin "3") (pinfunction "EN_3") (pintype "input"))
    )
    (net (code "23") (name "/TMI") (class "Default")
      (node (ref "J1") (pin "5") (pinfunction "KL_5") (pintype "passive"))
      (node (ref "U1") (pin "2") (pinfunction "CN/IN_2") (pintype "bidirectional"))
    )
    (net (code "24") (name "/TMO") (class "Default")
      (node (ref "J1") (pin "6") (pinfunction "KL_6") (pintype "passive"))
      (node (ref "U8") (pin "1") (pinfunction "OUT_1") (pintype "bidirectional"))
    )
    (net (code "25") (name "/VADC") (class "Default")
      (node (ref "C97") (pin "1") (pinfunction "1_1") (pintype "passive"))
      (node (ref "C98") (pin "1") (pinfunction "1_1") (pintype "passive"))
      (node (ref "R64") (pin "1") (pinfunction "1_1") (pintype "passive"))
      (node (ref "U18") (pin "16") (pinfunction "VDD_16") (pintype "bidirectional"))
    )
    (net (code "26") (name "/~{CS}") (class "Default")
      (node (ref "J1") (pin "4") (pinfunction "KL_4") (pintype "passive"))
      (node (ref "U18") (pin "11") (pinfunction "~{CS}_11") (pintype "bidirectional"))
    )
    (net (code "27") (name "GND") (class "Default")
      (node (ref "C27") (pin "1") (pinfunction "1_1") (pintype "passive"))
      (node (ref "C28") (pin "1") (pinfunction "1_1") (pintype "passive"))
      (node (ref "C29") (pin "1") (pinfunction "1_1") (pintype "passive"))
      (node (ref "C30") (pin "1") (pinfunction "1_1") (pintype "passive"))
      (node (ref "C31") (pin "1") (pinfunction "1_1") (pintype "passive"))
      (node (ref "C32") (pin "1") (pinfunction "1_1") (pintype "passive"))
      (node (ref "C33") (pin "1") (pinfunction "1_1") (pintype "passive"))
      (node (ref "C34") (pin "1") (pinfunction "1_1") (pintype "passive"))
      (node (ref "C43") (pin "1") (pinfunction "1_1") (pintype "passive"))
      (node (ref "C44") (pin "1") (pinfunction "1_1") (pintype "passive"))
      (node (ref "C45") (pin "1") (pinfunction "1_1") (pintype "passive"))
      (node (ref "C46") (pin "1") (pinfunction "1_1") (pintype "passive"))
      (node (ref "C47") (pin "1") (pinfunction "1_1") (pintype "passive"))
      (node (ref "C48") (pin "1") (pinfunction "1_1") (pintype "passive"))
      (node (ref "C49") (pin "1") (pinfunction "1_1") (pintype "passive"))
      (node (ref "C50") (pin "1") (pinfunction "1_1") (pintype "passive"))
      (node (ref "C52") (pin "1") (pinfunction "1_1") (pintype "passive"))
      (node (ref "C53") (pin "1") (pinfunction "1_1") (pintype "passive"))
      (node (ref "C54") (pin "1") (pinfunction "1_1") (pintype "passive"))
      (node (ref "C55") (pin "1") (pinfunction "1_1") (pintype "passive"))
      (node (ref "C56") (pin "1") (pinfunction "1_1") (pintype "passive"))
      (node (ref "C57") (pin "1") (pinfunction "1_1") (pintype "passive"))
      (node (ref "C58") (pin "1") (pinfunction "1_1") (pintype "passive"))
      (node (ref "C59") (pin "1") (pinfunction "1_1") (pintype "passive"))
      (node (ref "C63") (pin "C") (pinfunction "-_C") (pintype "passive"))
      (node (ref "C77") (pin "2") (pinfunction "2_2") (pintype "passive"))
      (node (ref "C78") (pin "2") (pinfunction "2_2") (pintype "passive"))
      (node (ref "C79") (pin "1") (pinfunction "1_1") (pintype "passive"))
      (node (ref "C80") (pin "1") (pinfunction "1_1") (pintype "passive"))
      (node (ref "C81") (pin "1") (pinfunction "1_1") (pintype "passive"))
      (node (ref "C82") (pin "1") (pinfunction "1_1") (pintype "passive"))
      (node (ref "C83") (pin "1") (pinfunction "1_1") (pintype "passive"))
      (node (ref "C84") (pin "1") (pinfunction "1_1") (pintype "passive"))
      (node (ref "C85") (pin "1") (pinfunction "1_1") (pintype "passive"))
      (node (ref "C86") (pin "1") (pinfunction "1_1") (pintype "passive"))
      (node (ref "C87") (pin "2") (pinfunction "2_2") (pintype "passive"))
      (node (ref "C88") (pin "2") (pinfunction "2_2") (pintype "passive"))
      (node (ref "C89") (pin "2") (pinfunction "2_2") (pintype "passive"))
      (node (ref "C90") (pin "2") (pinfunction "2_2") (pintype "passive"))
      (node (ref "C91") (pin "2") (pinfunction "2_2") (pintype "passive"))
      (node (ref "C92") (pin "2") (pinfunction "2_2") (pintype "passive"))
      (node (ref "C93") (pin "2") (pinfunction "2_2") (pintype "passive"))
      (node (ref "C94") (pin "2") (pinfunction "2_2") (pintype "passive"))
      (node (ref "C95") (pin "2") (pinfunction "2_2") (pintype "passive"))
      (node (ref "C96") (pin "2") (pinfunction "2_2") (pintype "passive"))
      (node (ref "C97") (pin "2") (pinfunction "2_2") (pintype "passive"))
      (node (ref "C98") (pin "2") (pinfunction "2_2") (pintype "passive"))
      (node (ref "J1") (pin "12") (pinfunction "KL_12") (pintype "passive"))
      (node (ref "SJ1") (pin "1") (pinfunction "1_1") (pintype "passive"))
      (node (ref "SJ2") (pin "2") (pinfunction "2_2") (pintype "passive"))
      (node (ref "SJ3") (pin "2") (pinfunction "2_2") (pintype "passive"))
      (node (ref "SJ4") (pin "2") (pinfunction "2_2") (pintype "passive"))
      (node (ref "SJ5") (pin "2") (pinfunction "2_2") (pintype "passive"))
      (node (ref "SJ6") (pin "2") (pinfunction "2_2") (pintype "passive"))
      (node (ref "SJ7") (pin "2") (pinfunction "2_2") (pintype "passive"))
      (node (ref "SJ8") (pin "2") (pinfunction "2_2") (pintype "passive"))
      (node (ref "U10") (pin "4") (pinfunction "V-_4") (pintype "power_in"))
      (node (ref "U11") (pin "4") (pinfunction "V-_4") (pintype "power_in"))
      (node (ref "U12") (pin "4") (pinfunction "V-_4") (pintype "power_in"))
      (node (ref "U13") (pin "4") (pinfunction "V-_4") (pintype "power_in"))
      (node (ref "U14") (pin "4") (pinfunction "V-_4") (pintype "power_in"))
      (node (ref "U15") (pin "4") (pinfunction "V-_4") (pintype "power_in"))
      (node (ref "U16") (pin "4") (pinfunction "V-_4") (pintype "power_in"))
      (node (ref "U17") (pin "4") (pinfunction "V-_4") (pintype "power_in"))
      (node (ref "U18") (pin "15") (pinfunction "GND_15") (pintype "bidirectional"))
    )
    (net (code "28") (name "Net-(C11-+)") (class "Default")
      (node (ref "C11") (pin "A") (pinfunction "+_A") (pintype "passive"))
      (node (ref "C26") (pin "1") (pinfunction "1_1") (pintype "passive"))
      (node (ref "R16") (pin "1") (pinfunction "1_1") (pintype "passive"))
      (node (ref "R17") (pin "2") (pinfunction "2_2") (pintype "passive"))
    )
    (net (code "29") (name "Net-(C12-+)") (class "Default")
      (node (ref "C12") (pin "A") (pinfunction "+_A") (pintype "passive"))
      (node (ref "C25") (pin "1") (pinfunction "1_1") (pintype "passive"))
      (node (ref "R11") (pin "1") (pinfunction "1_1") (pintype "passive"))
      (node (ref "R8") (pin "2") (pinfunction "2_2") (pintype "passive"))
    )
    (net (code "30") (name "Net-(C13-+)") (class "Default")
      (node (ref "C13") (pin "A") (pinfunction "+_A") (pintype "passive"))
      (node (ref "C19") (pin "1") (pinfunction "1_1") (pintype "passive"))
      (node (ref "R14") (pin "1") (pinfunction "1_1") (pintype "passive"))
      (node (ref "R15") (pin "2") (pinfunction "2_2") (pintype "passive"))
    )
    (net (code "31") (name "Net-(C15-+)") (class "Default")
      (node (ref "C15") (pin "A") (pinfunction "+_A") (pintype "passive"))
      (node (ref "C21") (pin "1") (pinfunction "1_1") (pintype "passive"))
      (node (ref "R12") (pin "1") (pinfunction "1_1") (pintype "passive"))
      (node (ref "R7") (pin "2") (pinfunction "2_2") (pintype "passive"))
    )
    (net (code "32") (name "Net-(C16-+)") (class "Default")
      (node (ref "C16") (pin "A") (pinfunction "+_A") (pintype "passive"))
      (node (ref "C24") (pin "1") (pinfunction "1_1") (pintype "passive"))
      (node (ref "R10") (pin "1") (pinfunction "1_1") (pintype "passive"))
      (node (ref "R6") (pin "2") (pinfunction "2_2") (pintype "passive"))
    )
    (net (code "33") (name "Net-(C17-+)") (class "Default")
      (node (ref "C17") (pin "A") (pinfunction "+_A") (pintype "passive"))
      (node (ref "C20") (pin "1") (pinfunction "1_1") (pintype "passive"))
      (node (ref "R3") (pin "1") (pinfunction "1_1") (pintype "passive"))
      (node (ref "R5") (pin "2") (pinfunction "2_2") (pintype "passive"))
    )
    (net (code "34") (name "Net-(C18-+)") (class "Default")
      (node (ref "C18") (pin "A") (pinfunction "+_A") (pintype "passive"))
      (node (ref "C22") (pin "1") (pinfunction "1_1") (pintype "passive"))
      (node (ref "R13") (pin "1") (pinfunction "1_1") (pintype "passive"))
      (node (ref "R9") (pin "2") (pinfunction "2_2") (pintype "passive"))
    )
    (net (code "35") (name "Net-(C35-1P)") (class "Default")
      (node (ref "C35") (pin "P") (pinfunction "1P_P") (pintype "passive"))
      (node (ref "M5") (pin "+") (pinfunction "OUT_+") (pintype "bidirectional"))
      (node (ref "R5") (pin "1") (pinfunction "1_1") (pintype "passive"))
    )
    (net (code "36") (name "Net-(C35-2M)") (class "Default")
      (node (ref "C35") (pin "M") (pinfunction "2M_M") (pintype "passive"))
      (node (ref "C69") (pin "2") (pinfunction "2_2") (pintype "passive"))
      (node (ref "R57") (pin "2") (pinfunction "2_2") (pintype "passive"))
      (node (ref "U12") (pin "2") (pinfunction "-IN_2") (pintype "input"))
    )
    (net (code "37") (name "Net-(C36-1P)") (class "Default")
      (node (ref "C36") (pin "P") (pinfunction "1P_P") (pintype "passive"))
      (node (ref "M4") (pin "+") (pinfunction "OUT_+") (pintype "bidirectional"))
      (node (ref "R8") (pin "1") (pinfunction "1_1") (pintype "passive"))
    )
    (net (code "38") (name "Net-(C36-2M)") (class "Default")
      (node (ref "C36") (pin "M") (pinfunction "2M_M") (pintype "passive"))
      (node (ref "C64") (pin "2") (pinfunction "2_2") (pintype "passive"))
      (node (ref "R52") (pin "2") (pinfunction "2_2") (pintype "passive"))
      (node (ref "U15") (pin "2") (pinfunction "-IN_2") (pintype "input"))
    )
    (net (code "39") (name "Net-(C37-1P)") (class "Default")
      (node (ref "C37") (pin "P") (pinfunction "1P_P") (pintype "passive"))
      (node (ref "M3") (pin "+") (pinfunction "OUT_+") (pintype "bidirectional"))
      (node (ref "R6") (pin "1") (pinfunction "1_1") (pintype "passive"))
    )
    (net (code "40") (name "Net-(C37-2M)") (class "Default")
      (node (ref "C37") (pin "M") (pinfunction "2M_M") (pintype "passive"))
      (node (ref "C67") (pin "2") (pinfunction "2_2") (pintype "passive"))
      (node (ref "R54") (pin "2") (pinfunction "2_2") (pintype "passive"))
      (node (ref "U13") (pin "2") (pinfunction "-IN_2") (pintype "input"))
    )
    (net (code "41") (name "Net-(C38-1P)") (class "Default")
      (node (ref "C38") (pin "P") (pinfunction "1P_P") (pintype "passive"))
      (node (ref "M6") (pin "+") (pinfunction "OUT_+") (pintype "bidirectional"))
      (node (ref "R7") (pin "1") (pinfunction "1_1") (pintype "passive"))
    )
    (net (code "42") (name "Net-(C38-2M)") (class "Default")
      (node (ref "C38") (pin "M") (pinfunction "2M_M") (pintype "passive"))
      (node (ref "C70") (pin "2") (pinfunction "2_2") (pintype "passive"))
      (node (ref "R56") (pin "2") (pinfunction "2_2") (pintype "passive"))
      (node (ref "U14") (pin "2") (pinfunction "-IN_2") (pintype "input"))
    )
    (net (code "43") (name "Net-(C39-1P)") (class "Default")
      (node (ref "C39") (pin "P") (pinfunction "1P_P") (pintype "passive"))
      (node (ref "M1") (pin "+") (pinfunction "OUT_+") (pintype "bidirectional"))
      (node (ref "R17") (pin "1") (pinfunction "1_1") (pintype "passive"))
    )
    (net (code "44") (name "Net-(C39-2M)") (class "Default")
      (node (ref "C39") (pin "M") (pinfunction "2M_M") (pintype "passive"))
      (node (ref "C62") (pin "2") (pinfunction "2_2") (pintype "passive"))
      (node (ref "R42") (pin "2") (pinfunction "2_2") (pintype "passive"))
      (node (ref "U10") (pin "2") (pinfunction "-IN_2") (pintype "input"))
    )
    (net (code "45") (name "Net-(C40-1P)") (class "Default")
      (node (ref "C40") (pin "P") (pinfunction "1P_P") (pintype "passive"))
      (node (ref "M2") (pin "+") (pinfunction "OUT_+") (pintype "bidirectional"))
      (node (ref "R4") (pin "1") (pinfunction "1_1") (pintype "passive"))
    )
    (net (code "46") (name "Net-(C40-2M)") (class "Default")
      (node (ref "C40") (pin "M") (pinfunction "2M_M") (pintype "passive"))
      (node (ref "C66") (pin "2") (pinfunction "2_2") (pintype "passive"))
      (node (ref "R55") (pin "2") (pinfunction "2_2") (pintype "passive"))
      (node (ref "U11") (pin "2") (pinfunction "-IN_2") (pintype "input"))
    )
    (net (code "47") (name "Net-(C41-1P)") (class "Default")
      (node (ref "C41") (pin "P") (pinfunction "1P_P") (pintype "passive"))
      (node (ref "M7") (pin "+") (pinfunction "OUT_+") (pintype "bidirectional"))
      (node (ref "R9") (pin "1") (pinfunction "1_1") (pintype "passive"))
    )
    (net (code "48") (name "Net-(C41-2M)") (class "Default")
      (node (ref "C41") (pin "M") (pinfunction "2M_M") (pintype "passive"))
      (node (ref "C65") (pin "2") (pinfunction "2_2") (pintype "passive"))
      (node (ref "R49") (pin "2") (pinfunction "2_2") (pintype "passive"))
      (node (ref "U16") (pin "2") (pinfunction "-IN_2") (pintype "input"))
    )
    (net (code "49") (name "Net-(C42-1P)") (class "Default")
      (node (ref "C42") (pin "P") (pinfunction "1P_P") (pintype "passive"))
      (node (ref "M8") (pin "+") (pinfunction "OUT_+") (pintype "bidirectional"))
      (node (ref "R15") (pin "1") (pinfunction "1_1") (pintype "passive"))
    )
    (net (code "50") (name "Net-(C42-2M)") (class "Default")
      (node (ref "C42") (pin "M") (pinfunction "2M_M") (pintype "passive"))
      (node (ref "C68") (pin "2") (pinfunction "2_2") (pintype "passive"))
      (node (ref "R46") (pin "2") (pinfunction "2_2") (pintype "passive"))
      (node (ref "U17") (pin "2") (pinfunction "-IN_2") (pintype "input"))
    )
    (net (code "51") (name "Net-(C43-Pad2)") (class "Default")
      (node (ref "C43") (pin "2") (pinfunction "2_2") (pintype "passive"))
      (node (ref "R26") (pin "2") (pinfunction "2_2") (pintype "passive"))
    )
    (net (code "52") (name "Net-(C44-Pad2)") (class "Default")
      (node (ref "C44") (pin "2") (pinfunction "2_2") (pintype "passive"))
      (node (ref "R27") (pin "2") (pinfunction "2_2") (pintype "passive"))
    )
    (net (code "53") (name "Net-(C45-Pad2)") (class "Default")
      (node (ref "C45") (pin "2") (pinfunction "2_2") (pintype "passive"))
      (node (ref "R28") (pin "2") (pinfunction "2_2") (pintype "passive"))
    )
    (net (code "54") (name "Net-(C46-Pad2)") (class "Default")
      (node (ref "C46") (pin "2") (pinfunction "2_2") (pintype "passive"))
      (node (ref "R29") (pin "2") (pinfunction "2_2") (pintype "passive"))
    )
    (net (code "55") (name "Net-(C47-Pad2)") (class "Default")
      (node (ref "C47") (pin "2") (pinfunction "2_2") (pintype "passive"))
      (node (ref "R30") (pin "2") (pinfunction "2_2") (pintype "passive"))
    )
    (net (code "56") (name "Net-(C48-Pad2)") (class "Default")
      (node (ref "C48") (pin "2") (pinfunction "2_2") (pintype "passive"))
      (node (ref "R31") (pin "2") (pinfunction "2_2") (pintype "passive"))
    )
    (net (code "57") (name "Net-(C49-Pad2)") (class "Default")
      (node (ref "C49") (pin "2") (pinfunction "2_2") (pintype "passive"))
      (node (ref "R32") (pin "2") (pinfunction "2_2") (pintype "passive"))
    )
    (net (code "58") (name "Net-(C50-Pad2)") (class "Default")
      (node (ref "C50") (pin "2") (pinfunction "2_2") (pintype "passive"))
      (node (ref "R33") (pin "2") (pinfunction "2_2") (pintype "passive"))
    )
    (net (code "59") (name "Net-(C60-Pad2)") (class "Default")
      (node (ref "C60") (pin "2") (pinfunction "2_2") (pintype "passive"))
      (node (ref "R19") (pin "2") (pinfunction "2_2") (pintype "passive"))
      (node (ref "R44") (pin "1") (pinfunction "1_1") (pintype "passive"))
    )
    (net (code "60") (name "Net-(C61-Pad2)") (class "Default")
      (node (ref "C61") (pin "2") (pinfunction "2_2") (pintype "passive"))
      (node (ref "R18") (pin "2") (pinfunction "2_2") (pintype "passive"))
      (node (ref "R43") (pin "1") (pinfunction "1_1") (pintype "passive"))
    )
    (net (code "61") (name "Net-(C71-Pad2)") (class "Default")
      (node (ref "C71") (pin "2") (pinfunction "2_2") (pintype "passive"))
      (node (ref "R20") (pin "2") (pinfunction "2_2") (pintype "passive"))
      (node (ref "R45") (pin "1") (pinfunction "1_1") (pintype "passive"))
    )
    (net (code "62") (name "Net-(C72-Pad2)") (class "Default")
      (node (ref "C72") (pin "2") (pinfunction "2_2") (pintype "passive"))
      (node (ref "R21") (pin "2") (pinfunction "2_2") (pintype "passive"))
      (node (ref "R47") (pin "1") (pinfunction "1_1") (pintype "passive"))
    )
    (net (code "63") (name "Net-(C73-Pad2)") (class "Default")
      (node (ref "C73") (pin "2") (pinfunction "2_2") (pintype "passive"))
      (node (ref "R22") (pin "2") (pinfunction "2_2") (pintype "passive"))
      (node (ref "R48") (pin "1") (pinfunction "1_1") (pintype "passive"))
    )
    (net (code "64") (name "Net-(C74-Pad2)") (class "Default")
      (node (ref "C74") (pin "2") (pinfunction "2_2") (pintype "passive"))
      (node (ref "R23") (pin "2") (pinfunction "2_2") (pintype "passive"))
      (node (ref "R50") (pin "1") (pinfunction "1_1") (pintype "passive"))
    )
    (net (code "65") (name "Net-(C75-Pad2)") (class "Default")
      (node (ref "C75") (pin "2") (pinfunction "2_2") (pintype "passive"))
      (node (ref "R24") (pin "2") (pinfunction "2_2") (pintype "passive"))
      (node (ref "R51") (pin "1") (pinfunction "1_1") (pintype "passive"))
    )
    (net (code "66") (name "Net-(C76-Pad2)") (class "Default")
      (node (ref "C76") (pin "2") (pinfunction "2_2") (pintype "passive"))
      (node (ref "R25") (pin "2") (pinfunction "2_2") (pintype "passive"))
      (node (ref "R53") (pin "1") (pinfunction "1_1") (pintype "passive"))
    )
    (net (code "67") (name "Net-(U1-OUT)") (class "Default")
      (node (ref "U1") (pin "1") (pinfunction "OUT_1") (pintype "bidirectional"))
      (node (ref "U2") (pin "2") (pinfunction "CN/IN_2") (pintype "bidirectional"))
    )
    (net (code "68") (name "Net-(U2-OUT)") (class "Default")
      (node (ref "U2") (pin "1") (pinfunction "OUT_1") (pintype "bidirectional"))
      (node (ref "U3") (pin "2") (pinfunction "CN/IN_2") (pintype "bidirectional"))
    )
    (net (code "69") (name "Net-(U3-OUT)") (class "Default")
      (node (ref "U3") (pin "1") (pinfunction "OUT_1") (pintype "bidirectional"))
      (node (ref "U4") (pin "2") (pinfunction "CN/IN_2") (pintype "bidirectional"))
    )
    (net (code "70") (name "Net-(U4-OUT)") (class "Default")
      (node (ref "U4") (pin "1") (pinfunction "OUT_1") (pintype "bidirectional"))
      (node (ref "U5") (pin "2") (pinfunction "CN/IN_2") (pintype "bidirectional"))
    )
    (net (code "71") (name "Net-(U5-OUT)") (class "Default")
      (node (ref "U5") (pin "1") (pinfunction "OUT_1") (pintype "bidirectional"))
      (node (ref "U6") (pin "2") (pinfunction "CN/IN_2") (pintype "bidirectional"))
    )
    (net (code "72") (name "Net-(U6-OUT)") (class "Default")
      (node (ref "U6") (pin "1") (pinfunction "OUT_1") (pintype "bidirectional"))
      (node (ref "U7") (pin "2") (pinfunction "CN/IN_2") (pintype "bidirectional"))
    )
    (net (code "73") (name "Net-(U7-OUT)") (class "Default")
      (node (ref "U7") (pin "1") (pinfunction "OUT_1") (pintype "bidirectional"))
      (node (ref "U8") (pin "2") (pinfunction "CN/IN_2") (pintype "bidirectional"))
    )
    (net (code "74") (name "Net-(U9-BP)") (class "Default")
      (node (ref "C10") (pin "1") (pinfunction "1_1") (pintype "passive"))
      (node (ref "U9") (pin "4") (pinfunction "BP_4") (pintype "input"))
    )
    (net (code "75") (name "Net-(U10A-OUT)") (class "Default")
      (node (ref "C62") (pin "1") (pinfunction "1_1") (pintype "passive"))
      (node (ref "R42") (pin "1") (pinfunction "1_1") (pintype "passive"))
      (node (ref "R43") (pin "2") (pinfunction "2_2") (pintype "passive"))
      (node (ref "U10") (pin "1") (pinfunction "OUT_1") (pintype "output"))
    )
    (net (code "76") (name "Net-(U10B-+IN)") (class "Default")
      (node (ref "C28") (pin "2") (pinfunction "2_2") (pintype "passive"))
      (node (ref "R18") (pin "1") (pinfunction "1_1") (pintype "passive"))
      (node (ref "U10") (pin "5") (pinfunction "+IN_5") (pintype "input"))
    )
    (net (code "77") (name "Net-(U10B--IN)") (class "Default")
      (node (ref "R33") (pin "1") (pinfunction "1_1") (pintype "passive"))
      (node (ref "R40") (pin "2") (pinfunction "2_2") (pintype "passive"))
      (node (ref "U10") (pin "6") (pinfunction "-IN_6") (pintype "input"))
    )
    (net (code "78") (name "Net-(U10B-OUT)") (class "Default")
      (node (ref "C61") (pin "1") (pinfunction "1_1") (pintype "passive"))
      (node (ref "R40") (pin "1") (pinfunction "1_1") (pintype "passive"))
      (node (ref "R58") (pin "2") (pinfunction "2_2") (pintype "passive"))
      (node (ref "U10") (pin "7") (pinfunction "OUT_7") (pintype "output"))
    )
    (net (code "79") (name "Net-(U11A-OUT)") (class "Default")
      (node (ref "C66") (pin "1") (pinfunction "1_1") (pintype "passive"))
      (node (ref "R44") (pin "2") (pinfunction "2_2") (pintype "passive"))
      (node (ref "R55") (pin "1") (pinfunction "1_1") (pintype "passive"))
      (node (ref "U11") (pin "1") (pinfunction "OUT_1") (pintype "output"))
    )
    (net (code "80") (name "Net-(U11B-+IN)") (class "Default")
      (node (ref "C27") (pin "2") (pinfunction "2_2") (pintype "passive"))
      (node (ref "R19") (pin "1") (pinfunction "1_1") (pintype "passive"))
      (node (ref "U11") (pin "5") (pinfunction "+IN_5") (pintype "input"))
    )
    (net (code "81") (name "Net-(U11B--IN)") (class "Default")
      (node (ref "R26") (pin "1") (pinfunction "1_1") (pintype "passive"))
      (node (ref "R34") (pin "2") (pinfunction "2_2") (pintype "passive"))
      (node (ref "U11") (pin "6") (pinfunction "-IN_6") (pintype "input"))
    )
    (net (code "82") (name "Net-(U11B-OUT)") (class "Default")
      (node (ref "C60") (pin "1") (pinfunction "1_1") (pintype "passive"))
      (node (ref "R34") (pin "1") (pinfunction "1_1") (pintype "passive"))
      (node (ref "R59") (pin "2") (pinfunction "2_2") (pintype "passive"))
      (node (ref "U11") (pin "7") (pinfunction "OUT_7") (pintype "output"))
    )
    (net (code "83") (name "Net-(U12A-OUT)") (class "Default")
      (node (ref "C69") (pin "1") (pinfunction "1_1") (pintype "passive"))
      (node (ref "R45") (pin "2") (pinfunction "2_2") (pintype "passive"))
      (node (ref "R57") (pin "1") (pinfunction "1_1") (pintype "passive"))
      (node (ref "U12") (pin "1") (pinfunction "OUT_1") (pintype "output"))
    )
    (net (code "84") (name "Net-(U12B-+IN)") (class "Default")
      (node (ref "C29") (pin "2") (pinfunction "2_2") (pintype "passive"))
      (node (ref "R20") (pin "1") (pinfunction "1_1") (pintype "passive"))
      (node (ref "U12") (pin "5") (pinfunction "+IN_5") (pintype "input"))
    )
    (net (code "85") (name "Net-(U12B--IN)") (class "Default")
      (node (ref "R27") (pin "1") (pinfunction "1_1") (pintype "passive"))
      (node (ref "R35") (pin "2") (pinfunction "2_2") (pintype "passive"))
      (node (ref "U12") (pin "6") (pinfunction "-IN_6") (pintype "input"))
    )
    (net (code "86") (name "Net-(U12B-OUT)") (class "Default")
      (node (ref "C71") (pin "1") (pinfunction "1_1") (pintype "passive"))
      (node (ref "R35") (pin "1") (pinfunction "1_1") (pintype "passive"))
      (node (ref "R62") (pin "2") (pinfunction "2_2") (pintype "passive"))
      (node (ref "U12") (pin "7") (pinfunction "OUT_7") (pintype "output"))
    )
    (net (code "87") (name "Net-(U13A-OUT)") (class "Default")
      (node (ref "C67") (pin "1") (pinfunction "1_1") (pintype "passive"))
      (node (ref "R47") (pin "2") (pinfunction "2_2") (pintype "passive"))
      (node (ref "R54") (pin "1") (pinfunction "1_1") (pintype "passive"))
      (node (ref "U13") (pin "1") (pinfunction "OUT_1") (pintype "output"))
    )
    (net (code "88") (name "Net-(U13B-+IN)") (class "Default")
      (node (ref "C30") (pin "2") (pinfunction "2_2") (pintype "passive"))
      (node (ref "R21") (pin "1") (pinfunction "1_1") (pintype "passive"))
      (node (ref "U13") (pin "5") (pinfunction "+IN_5") (pintype "input"))
    )
    (net (code "89") (name "Net-(U13B--IN)") (class "Default")
      (node (ref "R28") (pin "1") (pinfunction "1_1") (pintype "passive"))
      (node (ref "R36") (pin "2") (pinfunction "2_2") (pintype "passive"))
      (node (ref "U13") (pin "6") (pinfunction "-IN_6") (pintype "input"))
    )
    (net (code "90") (name "Net-(U13B-OUT)") (class "Default")
      (node (ref "C72") (pin "1") (pinfunction "1_1") (pintype "passive"))
      (node (ref "R36") (pin "1") (pinfunction "1_1") (pintype "passive"))
      (node (ref "R60") (pin "2") (pinfunction "2_2") (pintype "passive"))
      (node (ref "U13") (pin "7") (pinfunction "OUT_7") (pintype "output"))
    )
    (net (code "91") (name "Net-(U14A-OUT)") (class "Default")
      (node (ref "C70") (pin "1") (pinfunction "1_1") (pintype "passive"))
      (node (ref "R48") (pin "2") (pinfunction "2_2") (pintype "passive"))
      (node (ref "R56") (pin "1") (pinfunction "1_1") (pintype "passive"))
      (node (ref "U14") (pin "1") (pinfunction "OUT_1") (pintype "output"))
    )
    (net (code "92") (name "Net-(U14B-+IN)") (class "Default")
      (node (ref "C34") (pin "2") (pinfunction "2_2") (pintype "passive"))
      (node (ref "R22") (pin "1") (pinfunction "1_1") (pintype "passive"))
      (node (ref "U14") (pin "5") (pinfunction "+IN_5") (pintype "input"))
    )
    (net (code "93") (name "Net-(U14B--IN)") (class "Default")
      (node (ref "R29") (pin "1") (pinfunction "1_1") (pintype "passive"))
      (node (ref "R37") (pin "2") (pinfunction "2_2") (pintype "passive"))
      (node (ref "U14") (pin "6") (pinfunction "-IN_6") (pintype "input"))
    )
    (net (code "94") (name "Net-(U14B-OUT)") (class "Default")
      (node (ref "C73") (pin "1") (pinfunction "1_1") (pintype "passive"))
      (node (ref "R37") (pin "1") (pinfunction "1_1") (pintype "passive"))
      (node (ref "R63") (pin "2") (pinfunction "2_2") (pintype "passive"))
      (node (ref "U14") (pin "7") (pinfunction "OUT_7") (pintype "output"))
    )
    (net (code "95") (name "Net-(U15A-OUT)") (class "Default")
      (node (ref "C64") (pin "1") (pinfunction "1_1") (pintype "passive"))
      (node (ref "R50") (pin "2") (pinfunction "2_2") (pintype "passive"))
      (node (ref "R52") (pin "1") (pinfunction "1_1") (pintype "passive"))
      (node (ref "U15") (pin "1") (pinfunction "OUT_1") (pintype "output"))
    )
    (net (code "96") (name "Net-(U15B-+IN)") (class "Default")
      (node (ref "C31") (pin "2") (pinfunction "2_2") (pintype "passive"))
      (node (ref "R23") (pin "1") (pinfunction "1_1") (pintype "passive"))
      (node (ref "U15") (pin "5") (pinfunction "+IN_5") (pintype "input"))
    )
    (net (code "97") (name "Net-(U15B--IN)") (class "Default")
      (node (ref "R30") (pin "1") (pinfunction "1_1") (pintype "passive"))
      (node (ref "R38") (pin "2") (pinfunction "2_2") (pintype "passive"))
      (node (ref "U15") (pin "6") (pinfunction "-IN_6") (pintype "input"))
    )
    (net (code "98") (name "Net-(U16A-OUT)") (class "Default")
      (node (ref "C65") (pin "1") (pinfunction "1_1") (pintype "passive"))
      (node (ref "R49") (pin "1") (pinfunction "1_1") (pintype "passive"))
      (node (ref "R51") (pin "2") (pinfunction "2_2") (pintype "passive"))
      (node (ref "U16") (pin "1") (pinfunction "OUT_1") (pintype "output"))
    )
    (net (code "99") (name "Net-(U16B-+IN)") (class "Default")
      (node (ref "C32") (pin "2") (pinfunction "2_2") (pintype "passive"))
      (node (ref "R24") (pin "1") (pinfunction "1_1") (pintype "passive"))
      (node (ref "U16") (pin "5") (pinfunction "+IN_5") (pintype "input"))
    )
    (net (code "100") (name "Net-(U16B--IN)") (class "Default")
      (node (ref "R31") (pin "1") (pinfunction "1_1") (pintype "passive"))
      (node (ref "R39") (pin "2") (pinfunction "2_2") (pintype "passive"))
      (node (ref "U16") (pin "6") (pinfunction "-IN_6") (pintype "input"))
    )
    (net (code "101") (name "Net-(U16B-OUT)") (class "Default")
      (node (ref "C75") (pin "1") (pinfunction "1_1") (pintype "passive"))
      (node (ref "R39") (pin "1") (pinfunction "1_1") (pintype "passive"))
      (node (ref "R65") (pin "2") (pinfunction "2_2") (pintype "passive"))
      (node (ref "U16") (pin "7") (pinfunction "OUT_7") (pintype "output"))
    )
    (net (code "102") (name "Net-(U17A-OUT)") (class "Default")
      (node (ref "C68") (pin "1") (pinfunction "1_1") (pintype "passive"))
      (node (ref "R46") (pin "1") (pinfunction "1_1") (pintype "passive"))
      (node (ref "R53") (pin "2") (pinfunction "2_2") (pintype "passive"))
      (node (ref "U17") (pin "1") (pinfunction "OUT_1") (pintype "output"))
    )
    (net (code "103") (name "Net-(U17B-+IN)") (class "Default")
      (node (ref "C33") (pin "2") (pinfunction "2_2") (pintype "passive"))
      (node (ref "R25") (pin "1") (pinfunction "1_1") (pintype "passive"))
      (node (ref "U17") (pin "5") (pinfunction "+IN_5") (pintype "input"))
    )
    (net (code "104") (name "Net-(U17B--IN)") (class "Default")
      (node (ref "R32") (pin "1") (pinfunction "1_1") (pintype "passive"))
      (node (ref "R41") (pin "2") (pinfunction "2_2") (pintype "passive"))
      (node (ref "U17") (pin "6") (pinfunction "-IN_6") (pintype "input"))
    )
    (net (code "105") (name "Net-(U17B-OUT)") (class "Default")
      (node (ref "C76") (pin "1") (pinfunction "1_1") (pintype "passive"))
      (node (ref "R41") (pin "1") (pinfunction "1_1") (pintype "passive"))
      (node (ref "R66") (pin "2") (pinfunction "2_2") (pintype "passive"))
      (node (ref "U17") (pin "7") (pinfunction "OUT_7") (pintype "output"))
    )
    (net (code "106") (name "unconnected-(J1M-KL-Pad8)") (class "Default")
      (node (ref "J1") (pin "8") (pinfunction "KL_8") (pintype "passive"))
    )
  )
)
